# Clk_recovery.net
KiCad netlist of a schematic drawn in Altium Designer
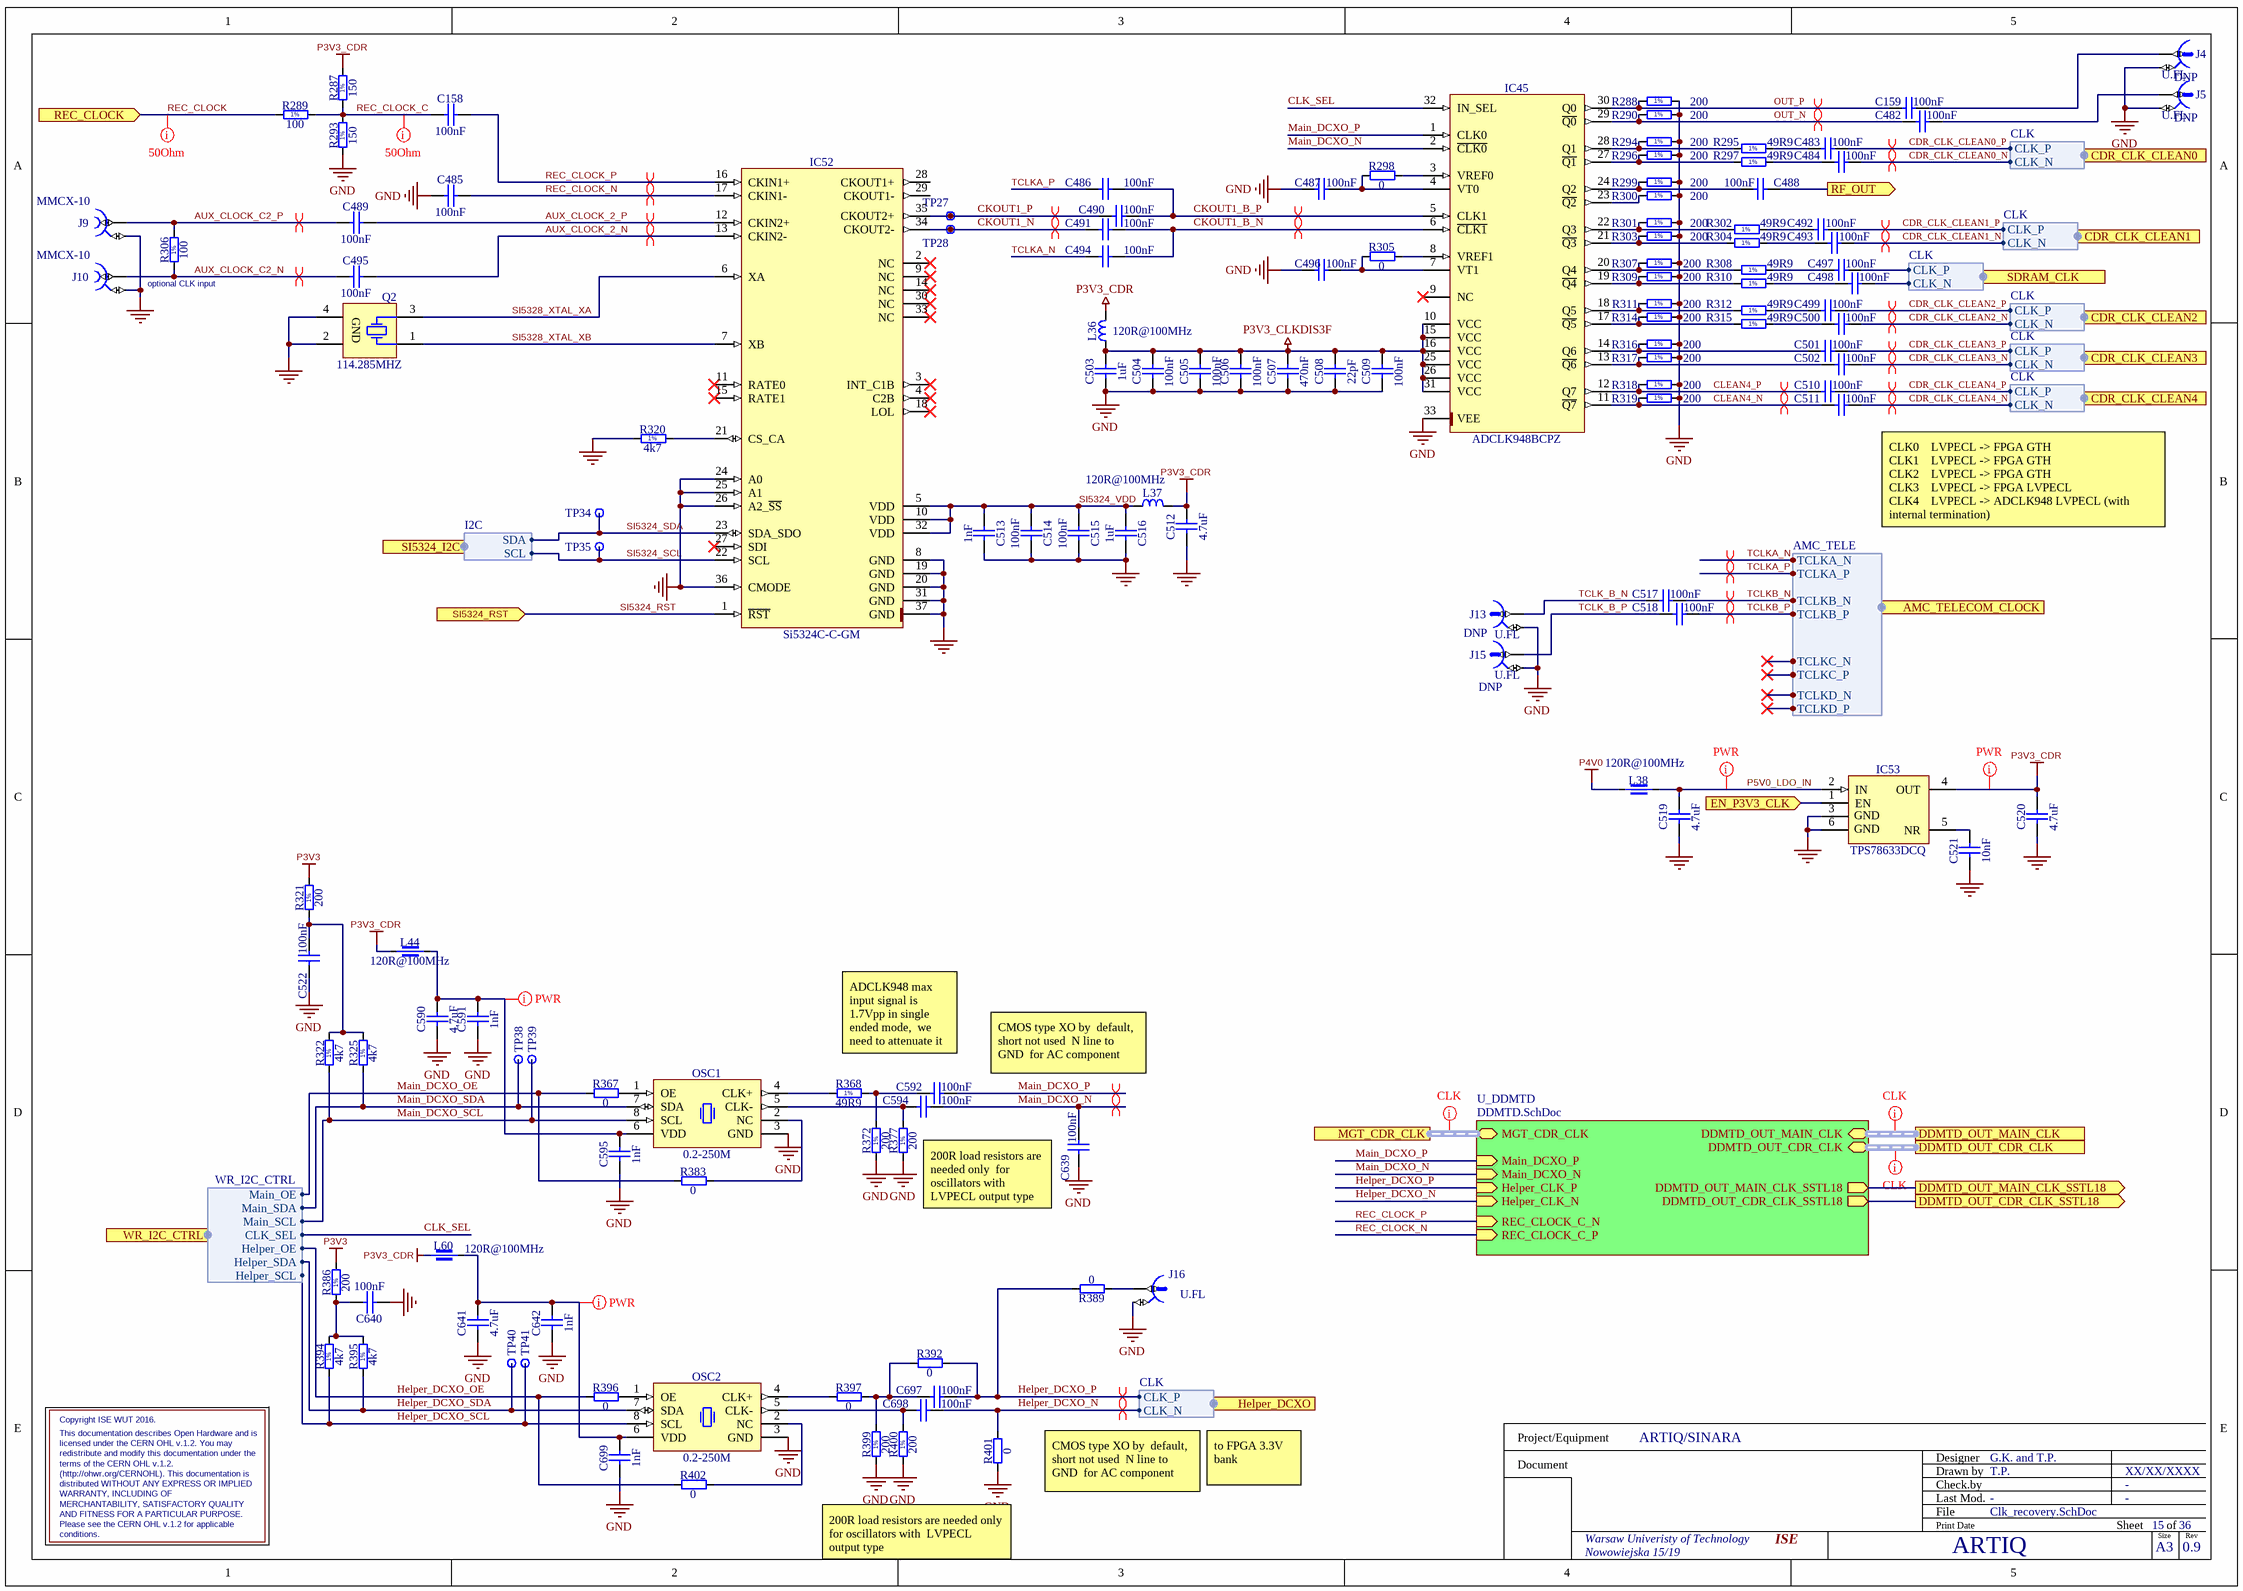
[diagram p0: Clk_recovery.SchDoc]

(export (version "E")
  (design (tool "Eeschema 10.0.6"))
  (components
    (comp (ref "C158")
      (value "100nF")
      (footprint "CAPC0603X33N")
      (description "Non-polarised capacitor")
      (fields
        (field (name "MANUFACTURER PART NUMBER") "CC0201_100NF_6.3V_10%_X5R")
        (field (name "MANUFACTURER") "GENERIC")
        (field (name "AUTHOR") "CERN DEM JLC")
      )
      (libsource (lib "Capacitors") (part "Capacitor - non polarized"))
    )
    (comp (ref "C159")
      (value "100nF")
      (footprint "CAPC0603X33N")
      (description "Non-polarised capacitor")
      (fields
        (field (name "MANUFACTURER PART NUMBER") "CC0201_100NF_6.3V_10%_X5R")
        (field (name "MANUFACTURER") "GENERIC")
        (field (name "AUTHOR") "CERN DEM JLC")
      )
      (libsource (lib "Capacitors") (part "Capacitor - non polarized"))
    )
    (comp (ref "C482")
      (value "100nF")
      (footprint "CAPC0603X33N")
      (description "Non-polarised capacitor")
      (fields
        (field (name "MANUFACTURER PART NUMBER") "CC0201_100NF_6.3V_10%_X5R")
        (field (name "MANUFACTURER") "GENERIC")
        (field (name "AUTHOR") "CERN DEM JLC")
      )
      (libsource (lib "Capacitors") (part "Capacitor - non polarized"))
    )
    (comp (ref "C483")
      (value "100nF")
      (footprint "CAPC0603X33N")
      (description "Non-polarised capacitor")
      (fields
        (field (name "MANUFACTURER PART NUMBER") "CC0201_100NF_6.3V_10%_X5R")
        (field (name "MANUFACTURER") "GENERIC")
        (field (name "AUTHOR") "CERN DEM JLC")
      )
      (libsource (lib "Capacitors") (part "Capacitor - non polarized"))
    )
    (comp (ref "C484")
      (value "100nF")
      (footprint "CAPC0603X33N")
      (description "Non-polarised capacitor")
      (fields
        (field (name "MANUFACTURER PART NUMBER") "CC0201_100NF_6.3V_10%_X5R")
        (field (name "MANUFACTURER") "GENERIC")
        (field (name "AUTHOR") "CERN DEM JLC")
      )
      (libsource (lib "Capacitors") (part "Capacitor - non polarized"))
    )
    (comp (ref "C485")
      (value "100nF")
      (footprint "CAPC0603X33N")
      (description "Non-polarised capacitor")
      (fields
        (field (name "MANUFACTURER PART NUMBER") "CC0201_100NF_6.3V_10%_X5R")
        (field (name "MANUFACTURER") "GENERIC")
        (field (name "AUTHOR") "CERN DEM JLC")
      )
      (libsource (lib "Capacitors") (part "Capacitor - non polarized"))
    )
    (comp (ref "C486")
      (value "100nF")
      (footprint "CAPC0603X33N")
      (description "Non-polarised capacitor")
      (fields
        (field (name "PART NUMBER") "CC0201_100NF_6.3V_10%_X5R")
        (field (name "VOLTAGE") "6.3V")
        (field (name "AUTHOR") "CERN DEM JLC")
      )
      (libsource (lib "Capacitors") (part "Capacitor - non polarized"))
    )
    (comp (ref "C487")
      (value "100nF")
      (footprint "CAPC0603X33N")
      (description "Non-polarised capacitor")
      (fields
        (field (name "PART NUMBER") "CC0201_100NF_6.3V_10%_X5R")
        (field (name "VOLTAGE") "6.3V")
        (field (name "AUTHOR") "CERN DEM JLC")
      )
      (libsource (lib "Capacitors") (part "Capacitor - non polarized"))
    )
    (comp (ref "C488")
      (value "100nF")
      (footprint "CAPC0603X33N")
      (description "Non-polarised capacitor")
      (fields
        (field (name "MANUFACTURER PART NUMBER") "CC0201_100NF_6.3V_10%_X5R")
        (field (name "MANUFACTURER") "GENERIC")
        (field (name "AUTHOR") "CERN DEM JLC")
      )
      (libsource (lib "Capacitors") (part "Capacitor - non polarized"))
    )
    (comp (ref "C489")
      (value "100nF")
      (footprint "CAPC0603X33N")
      (description "Non-polarised capacitor")
      (fields
        (field (name "MANUFACTURER PART NUMBER") "CC0201_100NF_6.3V_10%_X5R")
        (field (name "MANUFACTURER") "GENERIC")
        (field (name "AUTHOR") "CERN DEM JLC")
      )
      (libsource (lib "Capacitors") (part "Capacitor - non polarized"))
    )
    (comp (ref "C490")
      (value "100nF")
      (footprint "CAPC0603X33N")
      (description "Non-polarised capacitor")
      (fields
        (field (name "PART NUMBER") "CC0201_100NF_6.3V_10%_X5R")
        (field (name "VOLTAGE") "6.3V")
        (field (name "AUTHOR") "CERN DEM JLC")
      )
      (libsource (lib "Capacitors") (part "Capacitor - non polarized"))
    )
    (comp (ref "C491")
      (value "100nF")
      (footprint "CAPC0603X33N")
      (description "Non-polarised capacitor")
      (fields
        (field (name "PART NUMBER") "CC0201_100NF_6.3V_10%_X5R")
        (field (name "VOLTAGE") "6.3V")
        (field (name "AUTHOR") "CERN DEM JLC")
      )
      (libsource (lib "Capacitors") (part "Capacitor - non polarized"))
    )
    (comp (ref "C492")
      (value "100nF")
      (footprint "CAPC0603X33N")
      (description "Non-polarised capacitor")
      (fields
        (field (name "MANUFACTURER PART NUMBER") "CC0201_100NF_6.3V_10%_X5R")
        (field (name "MANUFACTURER") "GENERIC")
        (field (name "AUTHOR") "CERN DEM JLC")
      )
      (libsource (lib "Capacitors") (part "Capacitor - non polarized"))
    )
    (comp (ref "C493")
      (value "100nF")
      (footprint "CAPC0603X33N")
      (description "Non-polarised capacitor")
      (fields
        (field (name "MANUFACTURER PART NUMBER") "CC0201_100NF_6.3V_10%_X5R")
        (field (name "MANUFACTURER") "GENERIC")
        (field (name "AUTHOR") "CERN DEM JLC")
      )
      (libsource (lib "Capacitors") (part "Capacitor - non polarized"))
    )
    (comp (ref "C494")
      (value "100nF")
      (footprint "CAPC0603X33N")
      (description "Non-polarised capacitor")
      (fields
        (field (name "PART NUMBER") "CC0201_100NF_6.3V_10%_X5R")
        (field (name "VOLTAGE") "6.3V")
        (field (name "AUTHOR") "CERN DEM JLC")
      )
      (libsource (lib "Capacitors") (part "Capacitor - non polarized"))
    )
    (comp (ref "C495")
      (value "100nF")
      (footprint "CAPC0603X33N")
      (description "Non-polarised capacitor")
      (fields
        (field (name "MANUFACTURER PART NUMBER") "CC0201_100NF_6.3V_10%_X5R")
        (field (name "MANUFACTURER") "GENERIC")
        (field (name "AUTHOR") "CERN DEM JLC")
      )
      (libsource (lib "Capacitors") (part "Capacitor - non polarized"))
    )
    (comp (ref "C496")
      (value "100nF")
      (footprint "CAPC0603X33N")
      (description "Non-polarised capacitor")
      (fields
        (field (name "PART NUMBER") "CC0201_100NF_6.3V_10%_X5R")
        (field (name "VOLTAGE") "6.3V")
        (field (name "AUTHOR") "CERN DEM JLC")
      )
      (libsource (lib "Capacitors") (part "Capacitor - non polarized"))
    )
    (comp (ref "C497")
      (value "100nF")
      (footprint "CAPC0603X33N")
      (description "Non-polarised capacitor")
      (fields
        (field (name "MANUFACTURER PART NUMBER") "CC0201_100NF_6.3V_10%_X5R")
        (field (name "MANUFACTURER") "GENERIC")
        (field (name "AUTHOR") "CERN DEM JLC")
      )
      (libsource (lib "Capacitors") (part "Capacitor - non polarized"))
    )
    (comp (ref "C498")
      (value "100nF")
      (footprint "CAPC0603X33N")
      (description "Non-polarised capacitor")
      (fields
        (field (name "MANUFACTURER PART NUMBER") "CC0201_100NF_6.3V_10%_X5R")
        (field (name "MANUFACTURER") "GENERIC")
        (field (name "AUTHOR") "CERN DEM JLC")
      )
      (libsource (lib "Capacitors") (part "Capacitor - non polarized"))
    )
    (comp (ref "C499")
      (value "100nF")
      (footprint "CAPC0603X33N")
      (description "Non-polarised capacitor")
      (fields
        (field (name "MANUFACTURER PART NUMBER") "CC0201_100NF_6.3V_10%_X5R")
        (field (name "MANUFACTURER") "GENERIC")
        (field (name "AUTHOR") "CERN DEM JLC")
      )
      (libsource (lib "Capacitors") (part "Capacitor - non polarized"))
    )
    (comp (ref "C500")
      (value "100nF")
      (footprint "CAPC0603X33N")
      (description "Non-polarised capacitor")
      (fields
        (field (name "MANUFACTURER PART NUMBER") "CC0201_100NF_6.3V_10%_X5R")
        (field (name "MANUFACTURER") "GENERIC")
        (field (name "AUTHOR") "CERN DEM JLC")
      )
      (libsource (lib "Capacitors") (part "Capacitor - non polarized"))
    )
    (comp (ref "C501")
      (value "100nF")
      (footprint "CAPC0603X33N")
      (description "Non-polarised capacitor")
      (fields
        (field (name "MANUFACTURER PART NUMBER") "CC0201_100NF_6.3V_10%_X5R")
        (field (name "MANUFACTURER") "GENERIC")
        (field (name "AUTHOR") "CERN DEM JLC")
      )
      (libsource (lib "Capacitors") (part "Capacitor - non polarized"))
    )
    (comp (ref "C502")
      (value "100nF")
      (footprint "CAPC0603X33N")
      (description "Non-polarised capacitor")
      (fields
        (field (name "MANUFACTURER PART NUMBER") "CC0201_100NF_6.3V_10%_X5R")
        (field (name "MANUFACTURER") "GENERIC")
        (field (name "AUTHOR") "CERN DEM JLC")
      )
      (libsource (lib "Capacitors") (part "Capacitor - non polarized"))
    )
    (comp (ref "C503")
      (value "1uF")
      (footprint "CAPC1005X55N")
      (description "Non-polarised capacitor")
      (fields
        (field (name "PART NUMBER") "CC0402_1UF_16V_10%_X5R")
        (field (name "VOLTAGE") "16V")
        (field (name "AUTHOR") "CERN DEM JLC")
      )
      (libsource (lib "Capacitors") (part "Capacitor - non polarized"))
    )
    (comp (ref "C504")
      (value "100nF")
      (footprint "CAPC0603X33N")
      (description "Non-polarised capacitor")
      (fields
        (field (name "PART NUMBER") "CC0201_100NF_6.3V_10%_X5R")
        (field (name "VOLTAGE") "6.3V")
        (field (name "AUTHOR") "CERN DEM JLC")
      )
      (libsource (lib "Capacitors") (part "Capacitor - non polarized"))
    )
    (comp (ref "C505")
      (value "100nF")
      (footprint "CAPC0603X33N")
      (description "Non-polarised capacitor")
      (fields
        (field (name "PART NUMBER") "CC0201_100NF_6.3V_10%_X5R")
        (field (name "VOLTAGE") "6.3V")
        (field (name "AUTHOR") "CERN DEM JLC")
      )
      (libsource (lib "Capacitors") (part "Capacitor - non polarized"))
    )
    (comp (ref "C506")
      (value "100nF")
      (footprint "CAPC0603X33N")
      (description "Non-polarised capacitor")
      (fields
        (field (name "PART NUMBER") "CC0201_100NF_6.3V_10%_X5R")
        (field (name "VOLTAGE") "6.3V")
        (field (name "AUTHOR") "CERN DEM JLC")
      )
      (libsource (lib "Capacitors") (part "Capacitor - non polarized"))
    )
    (comp (ref "C507")
      (value "470nF")
      (footprint "CAPC1005X55N")
      (description "Non-polarised capacitor")
      (fields
        (field (name "PART NUMBER") "CC0402_470NF_16V_10%_X5R")
        (field (name "VOLTAGE") "16V")
        (field (name "AUTHOR") "CERN DEM JLC")
      )
      (libsource (lib "Capacitors") (part "Capacitor - non polarized"))
    )
    (comp (ref "C508")
      (value "22pF")
      (footprint "CAPC1005X55N")
      (description "Non-polarised capacitor")
      (fields
        (field (name "PART NUMBER") "CC0402_22PF_50V_5%_C0G")
        (field (name "VOLTAGE") "50V")
        (field (name "AUTHOR") "CERN DEM JLC")
      )
      (libsource (lib "Capacitors") (part "Capacitor - non polarized"))
    )
    (comp (ref "C509")
      (value "100nF")
      (footprint "CAPC0603X33N")
      (description "Non-polarised capacitor")
      (fields
        (field (name "PART NUMBER") "CC0201_100NF_6.3V_10%_X5R")
        (field (name "VOLTAGE") "6.3V")
        (field (name "AUTHOR") "CERN DEM JLC")
      )
      (libsource (lib "Capacitors") (part "Capacitor - non polarized"))
    )
    (comp (ref "C510")
      (value "100nF")
      (footprint "CAPC0603X33N")
      (description "Non-polarised capacitor")
      (fields
        (field (name "MANUFACTURER PART NUMBER") "CC0201_100NF_6.3V_10%_X5R")
        (field (name "MANUFACTURER") "GENERIC")
        (field (name "AUTHOR") "CERN DEM JLC")
      )
      (libsource (lib "Capacitors") (part "Capacitor - non polarized"))
    )
    (comp (ref "C511")
      (value "100nF")
      (footprint "CAPC0603X33N")
      (description "Non-polarised capacitor")
      (fields
        (field (name "MANUFACTURER PART NUMBER") "CC0201_100NF_6.3V_10%_X5R")
        (field (name "MANUFACTURER") "GENERIC")
        (field (name "AUTHOR") "CERN DEM JLC")
      )
      (libsource (lib "Capacitors") (part "Capacitor - non polarized"))
    )
    (comp (ref "C512")
      (value "4.7uF")
      (footprint "CAPC1608X90N")
      (description "Non-polarised capacitor")
      (fields
        (field (name "MANUFACTURER PART NUMBER") "CC0603_4.7UF_25V_10%_X5R")
        (field (name "MANUFACTURER") "GENERIC")
        (field (name "AUTHOR") "CERN DEM JLC")
      )
      (libsource (lib "Capacitors") (part "Capacitor - non polarized"))
    )
    (comp (ref "C513")
      (value "1nF")
      (footprint "CAPC0603X33N")
      (description "Non-polarised capacitor")
      (fields
        (field (name "MANUFACTURER PART NUMBER") "CC0201_1NF_16V_10%_X5R")
        (field (name "MANUFACTURER") "GENERIC")
        (field (name "AUTHOR") "CERN DEM JLC")
      )
      (libsource (lib "Capacitors") (part "Capacitor - non polarized"))
    )
    (comp (ref "C514")
      (value "100nF")
      (footprint "CAPC0603X33N")
      (description "Non-polarised capacitor")
      (fields
        (field (name "MANUFACTURER PART NUMBER") "CC0201_100NF_6.3V_10%_X5R")
        (field (name "MANUFACTURER") "GENERIC")
        (field (name "AUTHOR") "CERN DEM JLC")
      )
      (libsource (lib "Capacitors") (part "Capacitor - non polarized"))
    )
    (comp (ref "C515")
      (value "100nF")
      (footprint "CAPC0603X33N")
      (description "Non-polarised capacitor")
      (fields
        (field (name "MANUFACTURER PART NUMBER") "CC0201_100NF_6.3V_10%_X5R")
        (field (name "MANUFACTURER") "GENERIC")
        (field (name "AUTHOR") "CERN DEM JLC")
      )
      (libsource (lib "Capacitors") (part "Capacitor - non polarized"))
    )
    (comp (ref "C516")
      (value "1uF")
      (footprint "CAPC1005X55N")
      (description "Non-polarised capacitor")
      (fields
        (field (name "MANUFACTURER PART NUMBER") "CC0402_1UF_16V_10%_X5R")
        (field (name "MANUFACTURER") "GENERIC")
        (field (name "AUTHOR") "CERN DEM JLC")
      )
      (libsource (lib "Capacitors") (part "Capacitor - non polarized"))
    )
    (comp (ref "C517")
      (value "100nF")
      (footprint "CAPC0603X33N")
      (description "Non-polarised capacitor")
      (fields
        (field (name "MANUFACTURER PART NUMBER") "CC0201_100NF_6.3V_10%_X5R")
        (field (name "MANUFACTURER") "GENERIC")
        (field (name "AUTHOR") "CERN DEM JLC")
      )
      (libsource (lib "Capacitors") (part "Capacitor - non polarized"))
    )
    (comp (ref "C518")
      (value "100nF")
      (footprint "CAPC0603X33N")
      (description "Non-polarised capacitor")
      (fields
        (field (name "MANUFACTURER PART NUMBER") "CC0201_100NF_6.3V_10%_X5R")
        (field (name "MANUFACTURER") "GENERIC")
        (field (name "AUTHOR") "CERN DEM JLC")
      )
      (libsource (lib "Capacitors") (part "Capacitor - non polarized"))
    )
    (comp (ref "C519")
      (value "4.7uF")
      (footprint "CAPC1608X90N")
      (description "Non-polarised capacitor")
      (fields
        (field (name "MANUFACTURER PART NUMBER") "CC0603_4.7UF_25V_10%_X5R")
        (field (name "MANUFACTURER") "GENERIC")
        (field (name "AUTHOR") "CERN DEM JLC")
      )
      (libsource (lib "Capacitors") (part "Capacitor - non polarized"))
    )
    (comp (ref "C520")
      (value "4.7uF")
      (footprint "CAPC1608X90N")
      (description "Non-polarised capacitor")
      (fields
        (field (name "MANUFACTURER PART NUMBER") "CC0603_4.7UF_25V_10%_X5R")
        (field (name "MANUFACTURER") "GENERIC")
        (field (name "AUTHOR") "CERN DEM JLC")
      )
      (libsource (lib "Capacitors") (part "Capacitor - non polarized"))
    )
    (comp (ref "C521")
      (value "10nF")
      (footprint "CAPC1608X87N")
      (description "Non-polarised capacitor")
      (fields
        (field (name "PART NUMBER") "CC0603_10NF_50V_5%_C0G")
        (field (name "VOLTAGE") "50V")
        (field (name "AUTHOR") "CERN DEM JLC")
      )
      (libsource (lib "Capacitors") (part "Capacitor - non polarized"))
    )
    (comp (ref "C522")
      (value "100nF")
      (footprint "CAPC0603X33N")
      (description "Non-polarised capacitor")
      (fields
        (field (name "PART NUMBER") "CC0201_100NF_6.3V_10%_X5R")
        (field (name "VOLTAGE") "6.3V")
        (field (name "AUTHOR") "CERN DEM JLC")
      )
      (libsource (lib "Capacitors") (part "Capacitor - non polarized"))
    )
    (comp (ref "C590")
      (value "4.7uF")
      (footprint "CAPC1608X90N")
      (description "Non-polarised capacitor")
      (fields
        (field (name "PART NUMBER") "CC0603_4.7UF_25V_10%_X5R")
        (field (name "VOLTAGE") "25V")
        (field (name "AUTHOR") "CERN DEM JLC")
      )
      (libsource (lib "Capacitors") (part "Capacitor - non polarized"))
    )
    (comp (ref "C591")
      (value "1nF")
      (footprint "CAPC0603X33N")
      (description "Non-polarised capacitor")
      (fields
        (field (name "PART NUMBER") "CC0201_1NF_16V_10%_X5R")
        (field (name "VOLTAGE") "16V")
        (field (name "AUTHOR") "CERN DEM JLC")
      )
      (libsource (lib "Capacitors") (part "Capacitor - non polarized"))
    )
    (comp (ref "C592")
      (value "100nF")
      (footprint "CAPC0603X33N")
      (description "Non-polarised capacitor")
      (fields
        (field (name "PART NUMBER") "CC0201_100NF_6.3V_10%_X5R")
        (field (name "VOLTAGE") "6.3V")
        (field (name "AUTHOR") "CERN DEM JLC")
      )
      (libsource (lib "Capacitors") (part "Capacitor - non polarized"))
    )
    (comp (ref "C594")
      (value "100nF")
      (footprint "CAPC0603X33N")
      (description "Non-polarised capacitor")
      (fields
        (field (name "PART NUMBER") "CC0201_100NF_6.3V_10%_X5R")
        (field (name "VOLTAGE") "6.3V")
        (field (name "AUTHOR") "CERN DEM JLC")
      )
      (libsource (lib "Capacitors") (part "Capacitor - non polarized"))
    )
    (comp (ref "C595")
      (value "1nF")
      (footprint "CAPC0603X33N")
      (description "Non-polarised capacitor")
      (fields
        (field (name "PART NUMBER") "CC0201_1NF_16V_10%_X5R")
        (field (name "VOLTAGE") "16V")
        (field (name "AUTHOR") "CERN DEM JLC")
      )
      (libsource (lib "Capacitors") (part "Capacitor - non polarized"))
    )
    (comp (ref "C639")
      (value "100nF")
      (footprint "CAPC0603X33N")
      (description "Non-polarised capacitor")
      (fields
        (field (name "PART NUMBER") "CC0201_100NF_6.3V_10%_X5R")
        (field (name "VOLTAGE") "6.3V")
        (field (name "AUTHOR") "CERN DEM JLC")
      )
      (libsource (lib "Capacitors") (part "Capacitor - non polarized"))
    )
    (comp (ref "C640")
      (value "100nF")
      (footprint "CAPC0603X33N")
      (description "Non-polarised capacitor")
      (fields
        (field (name "MANUFACTURER PART NUMBER") "CC0201_100NF_6.3V_10%_X5R")
        (field (name "MANUFACTURER") "GENERIC")
        (field (name "AUTHOR") "CERN DEM JLC")
      )
      (libsource (lib "Capacitors") (part "Capacitor - non polarized"))
    )
    (comp (ref "C641")
      (value "4.7uF")
      (footprint "CAPC1608X90N")
      (description "Non-polarised capacitor")
      (fields
        (field (name "PART NUMBER") "CC0603_4.7UF_25V_10%_X5R")
        (field (name "VOLTAGE") "25V")
        (field (name "AUTHOR") "CERN DEM JLC")
      )
      (libsource (lib "Capacitors") (part "Capacitor - non polarized"))
    )
    (comp (ref "C642")
      (value "1nF")
      (footprint "CAPC0603X33N")
      (description "Non-polarised capacitor")
      (fields
        (field (name "PART NUMBER") "CC0201_1NF_16V_10%_X5R")
        (field (name "VOLTAGE") "16V")
        (field (name "AUTHOR") "CERN DEM JLC")
      )
      (libsource (lib "Capacitors") (part "Capacitor - non polarized"))
    )
    (comp (ref "C697")
      (value "100nF")
      (footprint "CAPC0603X33N")
      (description "Non-polarised capacitor")
      (fields
        (field (name "PART NUMBER") "CC0201_100NF_6.3V_10%_X5R")
        (field (name "VOLTAGE") "6.3V")
        (field (name "AUTHOR") "CERN DEM JLC")
      )
      (libsource (lib "Capacitors") (part "Capacitor - non polarized"))
    )
    (comp (ref "C698")
      (value "100nF")
      (footprint "CAPC0603X33N")
      (description "Non-polarised capacitor")
      (fields
        (field (name "PART NUMBER") "CC0201_100NF_6.3V_10%_X5R")
        (field (name "VOLTAGE") "6.3V")
        (field (name "AUTHOR") "CERN DEM JLC")
      )
      (libsource (lib "Capacitors") (part "Capacitor - non polarized"))
    )
    (comp (ref "C699")
      (value "1nF")
      (footprint "CAPC0603X33N")
      (description "Non-polarised capacitor")
      (fields
        (field (name "PART NUMBER") "CC0201_1NF_16V_10%_X5R")
        (field (name "VOLTAGE") "16V")
        (field (name "AUTHOR") "CERN DEM JLC")
      )
      (libsource (lib "Capacitors") (part "Capacitor - non polarized"))
    )
    (comp (ref "IC45")
      (value "ADCLK948BCPZ")
      (footprint "QFN50P500X500X80-33N-S285")
      (description "Two Selectable Inputs, 8 LVPECL Outputs, SiGe Clock Fanout Buffer")
      (fields (field (name "MANUFACTURER") "ANALOG DEVICES") (field (name "AUTHOR") "CERN DEM MR"))
      (libsource (lib "ICs And Semiconductors") (part "ADCLK948"))
    )
    (comp (ref "IC52")
      (value "Si5324C-C-GM")
      (footprint "QFN50P600X600X90-37N-S425")
      (description "Any Frequency Precision Clock Multiplier/Jitter Attenuator")
      (fields (field (name "MANUFACTURER") "SILICON LABS") (field (name "AUTHOR") "CERN DEM JLC"))
      (libsource (lib "ICs And Semiconductors") (part "Si5324"))
    )
    (comp (ref "IC53")
      (value "TPS78633DCQ")
      (footprint "SOT127P700X180-6N")
      (description "Ultralow-Noise, High-PSRR, Fast, RF, 1.5A Low-Dropout Linear Regulator")
      (fields (field (name "MANUFACTURER") "TEXAS INSTRUMENTS") (field (name "AUTHOR") "CERN DEM JMW"))
      (libsource (lib "ICs And Semiconductors") (part "TPS786xxDCQ"))
    )
    (comp (ref "J4")
      (value "U.FL")
      (footprint "HIROSE_U.FL-R-SMT-1(10)")
      (fields
        (field (name "PART NUMBER") "HIROSE_U.FL-R-SMT-1(10)")
        (field (name "MANUFACTURER") "HIROSE (HRS)")
        (field (name "MANUFACTURER PART NUMBER") "U.FL-R-SMT-1(10)")
        (field (name "ALTIUM_VALUE") "DNP")
        (field (name "AUTHOR") "CERN DEM JLC")
      )
      (libsource (lib "") (part "Coax_1Male_1Shield_1"))
    )
    (comp (ref "J5")
      (value "U.FL")
      (footprint "HIROSE_U.FL-R-SMT-1(10)")
      (fields
        (field (name "PART NUMBER") "HIROSE_U.FL-R-SMT-1(10)")
        (field (name "MANUFACTURER") "HIROSE (HRS)")
        (field (name "MANUFACTURER PART NUMBER") "U.FL-R-SMT-1(10)")
        (field (name "ALTIUM_VALUE") "DNP")
        (field (name "AUTHOR") "CERN DEM JLC")
      )
      (libsource (lib "") (part "Coax_1Male_1Shield_1"))
    )
    (comp (ref "J9")
      (value "Coax_1Female_1Shield")
      (footprint "NINIGI_MMCX-10")
      (fields
        (field (name "PART NUMBER") "MMCX-10")
        (field (name "MANUFACTURER") "NINIGI")
        (field (name "MANUFACTURER PART NUMBER") "NINIGI MMCX-10")
        (field (name "AUTHOR") "GK")
      )
      (libsource (lib "LIBRARY_SCH") (part "CON_RF_MMCX"))
    )
    (comp (ref "J10")
      (value "Coax_1Female_1Shield")
      (footprint "NINIGI_MMCX-10")
      (fields
        (field (name "PART NUMBER") "MMCX-10")
        (field (name "MANUFACTURER") "NINIGI")
        (field (name "MANUFACTURER PART NUMBER") "NINIGI MMCX-10")
        (field (name "AUTHOR") "GK")
      )
      (libsource (lib "LIBRARY_SCH") (part "CON_RF_MMCX"))
    )
    (comp (ref "J13")
      (value "U.FL")
      (footprint "HIROSE_U.FL-R-SMT-1(10)")
      (fields
        (field (name "PART NUMBER") "HIROSE_U.FL-R-SMT-1(10)")
        (field (name "MANUFACTURER") "HIROSE (HRS)")
        (field (name "MANUFACTURER PART NUMBER") "U.FL-R-SMT-1(10)")
        (field (name "ALTIUM_VALUE") "DNP")
        (field (name "AUTHOR") "CERN DEM JLC")
      )
      (libsource (lib "Connectors") (part "Coax_1Male_1Shield"))
    )
    (comp (ref "J15")
      (value "U.FL")
      (footprint "HIROSE_U.FL-R-SMT-1(10)")
      (fields
        (field (name "PART NUMBER") "HIROSE_U.FL-R-SMT-1(10)")
        (field (name "MANUFACTURER") "HIROSE (HRS)")
        (field (name "MANUFACTURER PART NUMBER") "U.FL-R-SMT-1(10)")
        (field (name "ALTIUM_VALUE") "DNP")
        (field (name "AUTHOR") "CERN DEM JLC")
      )
      (libsource (lib "Connectors") (part "Coax_1Male_1Shield"))
    )
    (comp (ref "J16")
      (value "U.FL")
      (footprint "HIROSE_U.FL-R-SMT-1(10)")
      (fields
        (field (name "MANUFACTURER PART NUMBER") "U.FL-R-SMT-1(10)")
        (field (name "MANUFACTURER") "HIROSE (HRS)")
        (field (name "PART NUMBER") "HIROSE_U.FL-R-SMT-1(10)")
        (field (name "AUTHOR") "CERN DEM JLC")
      )
      (libsource (lib "") (part "Coax_1Male_1Shield_1"))
    )
    (comp (ref "L36")
      (value "120R@100MHz")
      (footprint "INDC1608X95N")
      (description "Inductor")
      (fields
        (field (name "PART NUMBER") "IND0603_MURATA_BLM18PG121SN1D")
        (field (name "POWER") "2A")
        (field (name "AUTHOR") "CERN DEM BC")
      )
      (libsource (lib "") (part "Inductor_1"))
    )
    (comp (ref "L37")
      (value "120R@100MHz")
      (footprint "INDC1608X95N")
      (description "Inductor")
      (fields
        (field (name "MANUFACTURER PART NUMBER") "BLM18PG121SN1D")
        (field (name "MANUFACTURER") "MURATA")
        (field (name "AUTHOR") "CERN DEM BC")
      )
      (libsource (lib "Inductors & Transformers") (part "Inductor"))
    )
    (comp (ref "L38")
      (value "120R@100MHz")
      (footprint "INDC1608X95N")
      (fields
        (field (name "MANUFACTURER PART NUMBER") "BLM18PG121SN1D")
        (field (name "MANUFACTURER") "MURATA")
        (field (name "PART NUMBER") "IND0603_MURATA_BLM18PG121SN1D")
        (field (name "AUTHOR") "CERN DEM BC")
      )
      (libsource (lib "Inductors & Transformers") (part "Ferrite Bead"))
    )
    (comp (ref "L44")
      (value "120R@100MHz")
      (footprint "INDC1608X95N")
      (fields
        (field (name "PART NUMBER") "IND0603_MURATA_BLM18PG121SN1D")
        (field (name "POWER") "2A")
        (field (name "MANUFACTURER") "MURATA")
        (field (name "AUTHOR") "CERN DEM BC")
      )
      (libsource (lib "Inductors & Transformers") (part "Ferrite Bead"))
    )
    (comp (ref "L60")
      (value "120R@100MHz")
      (footprint "INDC1608X95N")
      (fields
        (field (name "PART NUMBER") "IND0603_MURATA_BLM18PG121SN1D")
        (field (name "POWER") "2A")
        (field (name "MANUFACTURER") "MURATA")
        (field (name "AUTHOR") "CERN DEM BC")
      )
      (libsource (lib "Inductors & Transformers") (part "Ferrite Bead"))
    )
    (comp (ref "OSC1")
      (value "0.2-250M")
      (footprint "OSC_SILICON-LAB_SI570")
      (description "Ultra Low Jitter I2C Programmable XO (95 fs), 0.2 to 250MHz")
      (fields
        (field (name "MANUFACTURER") "Silabs")
        (field (name "MANUFACTURER PART NUMBER") "549CBAC000112ABG")
      )
      (libsource (lib "TP_LIB") (part "549CBAC000112ABG"))
    )
    (comp (ref "OSC2")
      (value "0.2-250M")
      (footprint "OSC_SILICON-LAB_SI570")
      (description "Ultra Low Jitter I2C Programmable XO (95 fs), 0.2 to 250MHz")
      (fields
        (field (name "MANUFACTURER") "Silabs")
        (field (name "MANUFACTURER PART NUMBER") "549CBAC000112ABG")
      )
      (libsource (lib "TP_LIB") (part "549CBAC000112ABG"))
    )
    (comp (ref "Q2")
      (value "114.285MHZ")
      (footprint "XTAL_CONNOR_CS")
      (description "Crystal 4 pins 1=XTAL Control 2=GND3=XTAL 4=GND")
      (fields
        (field (name "MANUFACTURER PART NUMBER") "CS-023-114.285M")
        (field (name "MANUFACTURER") "CONNOR-WINFIELD")
        (field (name "AUTHOR") "CERN DEM JLC")
      )
      (libsource (lib "ICs And Semiconductors") (part "Quartz Crystal 1X 2GND 3X 4GND"))
    )
    (comp (ref "R287")
      (value "150")
      (footprint "RESC1005X40N")
      (description "Resistor - 1%")
      (fields
        (field (name "PART NUMBER") "R0402_150R_1%_0.0625W_100PPM")
        (field (name "POWER") "0.0625W")
        (field (name "AUTHOR") "CERN DEM JLC")
      )
      (libsource (lib "Resistors") (part "Resistor - 1%"))
    )
    (comp (ref "R288")
      (value "200")
      (footprint "RESC1005X40N")
      (description "Resistor - 1%")
      (fields
        (field (name "MANUFACTURER PART NUMBER") "R0402_200R_1%_0.0625W_100PPM")
        (field (name "MANUFACTURER") "GENERIC")
        (field (name "AUTHOR") "CERN DEM JLC")
      )
      (libsource (lib "Resistors") (part "Resistor - 1%"))
    )
    (comp (ref "R289")
      (value "100")
      (footprint "RESC1005X40N")
      (description "Resistor - 1%")
      (fields
        (field (name "MANUFACTURER PART NUMBER") "R0402_100R_1%_0.0625W_100PPM")
        (field (name "MANUFACTURER") "GENERIC")
        (field (name "AUTHOR") "CERN DEM JLC")
      )
      (libsource (lib "Resistors") (part "Resistor - 1%"))
    )
    (comp (ref "R290")
      (value "200")
      (footprint "RESC1005X40N")
      (description "Resistor - 1%")
      (fields
        (field (name "MANUFACTURER PART NUMBER") "R0402_200R_1%_0.0625W_100PPM")
        (field (name "MANUFACTURER") "GENERIC")
        (field (name "AUTHOR") "CERN DEM JLC")
      )
      (libsource (lib "Resistors") (part "Resistor - 1%"))
    )
    (comp (ref "R293")
      (value "150")
      (footprint "RESC1005X40N")
      (description "Resistor - 1%")
      (fields
        (field (name "PART NUMBER") "R0402_150R_1%_0.0625W_100PPM")
        (field (name "POWER") "0.0625W")
        (field (name "AUTHOR") "CERN DEM JLC")
      )
      (libsource (lib "Resistors") (part "Resistor - 1%"))
    )
    (comp (ref "R294")
      (value "200")
      (footprint "RESC1005X40N")
      (description "Resistor - 1%")
      (fields
        (field (name "MANUFACTURER PART NUMBER") "R0402_200R_1%_0.0625W_100PPM")
        (field (name "MANUFACTURER") "GENERIC")
        (field (name "AUTHOR") "CERN DEM JLC")
      )
      (libsource (lib "Resistors") (part "Resistor - 1%"))
    )
    (comp (ref "R295")
      (value "49R9")
      (footprint "RESC1005X40N")
      (description "Resistor - 1%")
      (fields
        (field (name "MANUFACTURER PART NUMBER") "R0402_49R9_1%_0.0625W_100PPM")
        (field (name "MANUFACTURER") "GENERIC")
        (field (name "AUTHOR") "CERN DEM JLC")
      )
      (libsource (lib "Resistors") (part "Resistor - 1%"))
    )
    (comp (ref "R296")
      (value "200")
      (footprint "RESC1005X40N")
      (description "Resistor - 1%")
      (fields
        (field (name "MANUFACTURER PART NUMBER") "R0402_200R_1%_0.0625W_100PPM")
        (field (name "MANUFACTURER") "GENERIC")
        (field (name "AUTHOR") "CERN DEM JLC")
      )
      (libsource (lib "Resistors") (part "Resistor - 1%"))
    )
    (comp (ref "R297")
      (value "49R9")
      (footprint "RESC1005X40N")
      (description "Resistor - 1%")
      (fields
        (field (name "MANUFACTURER PART NUMBER") "R0402_49R9_1%_0.0625W_100PPM")
        (field (name "MANUFACTURER") "GENERIC")
        (field (name "AUTHOR") "CERN DEM JLC")
      )
      (libsource (lib "Resistors") (part "Resistor - 1%"))
    )
    (comp (ref "R298")
      (value "0")
      (footprint "RESC1005X40N")
      (description "Resistor")
      (fields
        (field (name "PART NUMBER") "R0402_0R_JUMPER")
        (field (name "MANUFACTURER") "GENERIC")
        (field (name "AUTHOR") "CERN DEM JLC")
      )
      (libsource (lib "Resistors") (part "Resistor"))
    )
    (comp (ref "R299")
      (value "200")
      (footprint "RESC1005X40N")
      (description "Resistor - 1%")
      (fields
        (field (name "MANUFACTURER PART NUMBER") "R0402_200R_1%_0.0625W_100PPM")
        (field (name "MANUFACTURER") "GENERIC")
        (field (name "AUTHOR") "CERN DEM JLC")
      )
      (libsource (lib "Resistors") (part "Resistor - 1%"))
    )
    (comp (ref "R300")
      (value "200")
      (footprint "RESC1005X40N")
      (description "Resistor - 1%")
      (fields
        (field (name "MANUFACTURER PART NUMBER") "R0402_200R_1%_0.0625W_100PPM")
        (field (name "MANUFACTURER") "GENERIC")
        (field (name "AUTHOR") "CERN DEM JLC")
      )
      (libsource (lib "Resistors") (part "Resistor - 1%"))
    )
    (comp (ref "R301")
      (value "200")
      (footprint "RESC1005X40N")
      (description "Resistor - 1%")
      (fields
        (field (name "MANUFACTURER PART NUMBER") "R0402_200R_1%_0.0625W_100PPM")
        (field (name "MANUFACTURER") "GENERIC")
        (field (name "AUTHOR") "CERN DEM JLC")
      )
      (libsource (lib "Resistors") (part "Resistor - 1%"))
    )
    (comp (ref "R302")
      (value "49R9")
      (footprint "RESC1005X40N")
      (description "Resistor - 1%")
      (fields
        (field (name "MANUFACTURER PART NUMBER") "R0402_49R9_1%_0.0625W_100PPM")
        (field (name "MANUFACTURER") "GENERIC")
        (field (name "AUTHOR") "CERN DEM JLC")
      )
      (libsource (lib "Resistors") (part "Resistor - 1%"))
    )
    (comp (ref "R303")
      (value "200")
      (footprint "RESC1005X40N")
      (description "Resistor - 1%")
      (fields
        (field (name "MANUFACTURER PART NUMBER") "R0402_200R_1%_0.0625W_100PPM")
        (field (name "MANUFACTURER") "GENERIC")
        (field (name "AUTHOR") "CERN DEM JLC")
      )
      (libsource (lib "Resistors") (part "Resistor - 1%"))
    )
    (comp (ref "R304")
      (value "49R9")
      (footprint "RESC1005X40N")
      (description "Resistor - 1%")
      (fields
        (field (name "MANUFACTURER PART NUMBER") "R0402_49R9_1%_0.0625W_100PPM")
        (field (name "MANUFACTURER") "GENERIC")
        (field (name "AUTHOR") "CERN DEM JLC")
      )
      (libsource (lib "Resistors") (part "Resistor - 1%"))
    )
    (comp (ref "R305")
      (value "0")
      (footprint "RESC1005X40N")
      (description "Resistor")
      (fields
        (field (name "PART NUMBER") "R0402_0R_JUMPER")
        (field (name "MANUFACTURER") "GENERIC")
        (field (name "AUTHOR") "CERN DEM JLC")
      )
      (libsource (lib "Resistors") (part "Resistor"))
    )
    (comp (ref "R306")
      (value "100")
      (footprint "RESC1005X40N")
      (description "Resistor - 1%")
      (fields
        (field (name "MANUFACTURER PART NUMBER") "R0402_100R_1%_0.0625W_100PPM")
        (field (name "MANUFACTURER") "GENERIC")
        (field (name "AUTHOR") "CERN DEM JLC")
      )
      (libsource (lib "Resistors") (part "Resistor - 1%"))
    )
    (comp (ref "R307")
      (value "200")
      (footprint "RESC1005X40N")
      (description "Resistor - 1%")
      (fields
        (field (name "MANUFACTURER PART NUMBER") "R0402_200R_1%_0.0625W_100PPM")
        (field (name "MANUFACTURER") "GENERIC")
        (field (name "AUTHOR") "CERN DEM JLC")
      )
      (libsource (lib "Resistors") (part "Resistor - 1%"))
    )
    (comp (ref "R308")
      (value "49R9")
      (footprint "RESC1005X40N")
      (description "Resistor - 1%")
      (fields
        (field (name "MANUFACTURER PART NUMBER") "R0402_49R9_1%_0.0625W_100PPM")
        (field (name "MANUFACTURER") "GENERIC")
        (field (name "AUTHOR") "CERN DEM JLC")
      )
      (libsource (lib "Resistors") (part "Resistor - 1%"))
    )
    (comp (ref "R309")
      (value "200")
      (footprint "RESC1005X40N")
      (description "Resistor - 1%")
      (fields
        (field (name "MANUFACTURER PART NUMBER") "R0402_200R_1%_0.0625W_100PPM")
        (field (name "MANUFACTURER") "GENERIC")
        (field (name "AUTHOR") "CERN DEM JLC")
      )
      (libsource (lib "Resistors") (part "Resistor - 1%"))
    )
    (comp (ref "R310")
      (value "49R9")
      (footprint "RESC1005X40N")
      (description "Resistor - 1%")
      (fields
        (field (name "MANUFACTURER PART NUMBER") "R0402_49R9_1%_0.0625W_100PPM")
        (field (name "MANUFACTURER") "GENERIC")
        (field (name "AUTHOR") "CERN DEM JLC")
      )
      (libsource (lib "Resistors") (part "Resistor - 1%"))
    )
    (comp (ref "R311")
      (value "200")
      (footprint "RESC1005X40N")
      (description "Resistor - 1%")
      (fields
        (field (name "MANUFACTURER PART NUMBER") "R0402_200R_1%_0.0625W_100PPM")
        (field (name "MANUFACTURER") "GENERIC")
        (field (name "AUTHOR") "CERN DEM JLC")
      )
      (libsource (lib "Resistors") (part "Resistor - 1%"))
    )
    (comp (ref "R312")
      (value "49R9")
      (footprint "RESC1005X40N")
      (description "Resistor - 1%")
      (fields
        (field (name "MANUFACTURER PART NUMBER") "R0402_49R9_1%_0.0625W_100PPM")
        (field (name "MANUFACTURER") "GENERIC")
        (field (name "AUTHOR") "CERN DEM JLC")
      )
      (libsource (lib "Resistors") (part "Resistor - 1%"))
    )
    (comp (ref "R314")
      (value "200")
      (footprint "RESC1005X40N")
      (description "Resistor - 1%")
      (fields
        (field (name "MANUFACTURER PART NUMBER") "R0402_200R_1%_0.0625W_100PPM")
        (field (name "MANUFACTURER") "GENERIC")
        (field (name "AUTHOR") "CERN DEM JLC")
      )
      (libsource (lib "Resistors") (part "Resistor - 1%"))
    )
    (comp (ref "R315")
      (value "49R9")
      (footprint "RESC1005X40N")
      (description "Resistor - 1%")
      (fields
        (field (name "MANUFACTURER PART NUMBER") "R0402_49R9_1%_0.0625W_100PPM")
        (field (name "MANUFACTURER") "GENERIC")
        (field (name "AUTHOR") "CERN DEM JLC")
      )
      (libsource (lib "Resistors") (part "Resistor - 1%"))
    )
    (comp (ref "R316")
      (value "200")
      (footprint "RESC1005X40N")
      (description "Resistor - 1%")
      (fields
        (field (name "MANUFACTURER PART NUMBER") "R0402_200R_1%_0.0625W_100PPM")
        (field (name "MANUFACTURER") "GENERIC")
        (field (name "AUTHOR") "CERN DEM JLC")
      )
      (libsource (lib "Resistors") (part "Resistor - 1%"))
    )
    (comp (ref "R317")
      (value "200")
      (footprint "RESC1005X40N")
      (description "Resistor - 1%")
      (fields
        (field (name "MANUFACTURER PART NUMBER") "R0402_200R_1%_0.0625W_100PPM")
        (field (name "MANUFACTURER") "GENERIC")
        (field (name "AUTHOR") "CERN DEM JLC")
      )
      (libsource (lib "Resistors") (part "Resistor - 1%"))
    )
    (comp (ref "R318")
      (value "200")
      (footprint "RESC1005X40N")
      (description "Resistor - 1%")
      (fields
        (field (name "MANUFACTURER PART NUMBER") "R0402_200R_1%_0.0625W_100PPM")
        (field (name "MANUFACTURER") "GENERIC")
        (field (name "AUTHOR") "CERN DEM JLC")
      )
      (libsource (lib "Resistors") (part "Resistor - 1%"))
    )
    (comp (ref "R319")
      (value "200")
      (footprint "RESC1005X40N")
      (description "Resistor - 1%")
      (fields
        (field (name "MANUFACTURER PART NUMBER") "R0402_200R_1%_0.0625W_100PPM")
        (field (name "MANUFACTURER") "GENERIC")
        (field (name "AUTHOR") "CERN DEM JLC")
      )
      (libsource (lib "Resistors") (part "Resistor - 1%"))
    )
    (comp (ref "R320")
      (value "4k7")
      (footprint "RESC1005X40N")
      (description "Resistor - 1%")
      (fields
        (field (name "MANUFACTURER PART NUMBER") "R0402_4K7_1%_0.0625W_100PPM")
        (field (name "MANUFACTURER") "GENERIC")
        (field (name "AUTHOR") "CERN DEM JLC")
      )
      (libsource (lib "Resistors") (part "Resistor - 1%"))
    )
    (comp (ref "R321")
      (value "200")
      (footprint "RESC1005X40N")
      (description "Resistor - 1%")
      (fields
        (field (name "PART NUMBER") "R0402_200R_1%_0.0625W_100PPM")
        (field (name "POWER") "0.0625W")
        (field (name "AUTHOR") "CERN DEM JLC")
      )
      (libsource (lib "Resistors") (part "Resistor - 1%"))
    )
    (comp (ref "R322")
      (value "4k7")
      (footprint "RESC1005X40N")
      (description "Resistor - 1%")
      (fields
        (field (name "PART NUMBER") "R0402_4K7_1%_0.0625W_100PPM")
        (field (name "POWER") "0.0625W")
        (field (name "AUTHOR") "CERN DEM JLC")
      )
      (libsource (lib "Resistors") (part "Resistor - 1%"))
    )
    (comp (ref "R325")
      (value "4k7")
      (footprint "RESC1005X40N")
      (description "Resistor - 1%")
      (fields
        (field (name "PART NUMBER") "R0402_4K7_1%_0.0625W_100PPM")
        (field (name "POWER") "0.0625W")
        (field (name "AUTHOR") "CERN DEM JLC")
      )
      (libsource (lib "Resistors") (part "Resistor - 1%"))
    )
    (comp (ref "R367")
      (value "0")
      (footprint "RESC1005X40N")
      (description "Resistor")
      (fields
        (field (name "PART NUMBER") "R0402_0R_JUMPER")
        (field (name "MANUFACTURER") "GENERIC")
        (field (name "AUTHOR") "CERN DEM JLC")
      )
      (libsource (lib "Resistors") (part "Resistor"))
    )
    (comp (ref "R368")
      (value "49R9")
      (footprint "RESC1005X40N")
      (description "Resistor - 1%")
      (fields
        (field (name "MANUFACTURER PART NUMBER") "R0402_49R9_1%_0.0625W_100PPM")
        (field (name "MANUFACTURER") "GENERIC")
        (field (name "AUTHOR") "CERN DEM JLC")
      )
      (libsource (lib "Resistors") (part "Resistor - 1%"))
    )
    (comp (ref "R372")
      (value "200")
      (footprint "RESC1005X40N")
      (description "Resistor - 1%")
      (fields
        (field (name "PART NUMBER") "R0402_200R_1%_0.0625W_100PPM")
        (field (name "POWER") "0.0625W")
        (field (name "AUTHOR") "CERN DEM JLC")
      )
      (libsource (lib "Resistors") (part "Resistor - 1%"))
    )
    (comp (ref "R377")
      (value "200")
      (footprint "RESC1005X40N")
      (description "Resistor - 1%")
      (fields
        (field (name "PART NUMBER") "R0402_200R_1%_0.0625W_100PPM")
        (field (name "POWER") "0.0625W")
        (field (name "AUTHOR") "CERN DEM JLC")
      )
      (libsource (lib "Resistors") (part "Resistor - 1%"))
    )
    (comp (ref "R383")
      (value "0")
      (footprint "RESC1005X40N")
      (description "Resistor")
      (fields
        (field (name "PART NUMBER") "R0402_0R_JUMPER")
        (field (name "MANUFACTURER") "GENERIC")
        (field (name "AUTHOR") "CERN DEM JLC")
      )
      (libsource (lib "Resistors") (part "Resistor"))
    )
    (comp (ref "R386")
      (value "200")
      (footprint "RESC1005X40N")
      (description "Resistor - 1%")
      (fields
        (field (name "PART NUMBER") "R0402_200R_1%_0.0625W_100PPM")
        (field (name "POWER") "0.0625W")
        (field (name "AUTHOR") "CERN DEM JLC")
      )
      (libsource (lib "Resistors") (part "Resistor - 1%"))
    )
    (comp (ref "R389")
      (value "0")
      (footprint "RESC1005X40N")
      (description "Resistor")
      (fields
        (field (name "MANUFACTURER PART NUMBER") "R0402_0R_JUMPER")
        (field (name "MANUFACTURER") "GENERIC")
        (field (name "AUTHOR") "CERN DEM JLC")
      )
      (libsource (lib "Resistors") (part "Resistor"))
    )
    (comp (ref "R392")
      (value "0")
      (footprint "RESC1005X40N")
      (description "Resistor")
      (fields
        (field (name "PART NUMBER") "R0402_0R_JUMPER")
        (field (name "MANUFACTURER") "GENERIC")
        (field (name "AUTHOR") "CERN DEM JLC")
      )
      (libsource (lib "Resistors") (part "Resistor"))
    )
    (comp (ref "R394")
      (value "4k7")
      (footprint "RESC1005X40N")
      (description "Resistor - 1%")
      (fields
        (field (name "PART NUMBER") "R0402_4K7_1%_0.0625W_100PPM")
        (field (name "POWER") "0.0625W")
        (field (name "AUTHOR") "CERN DEM JLC")
      )
      (libsource (lib "Resistors") (part "Resistor - 1%"))
    )
    (comp (ref "R395")
      (value "4k7")
      (footprint "RESC1005X40N")
      (description "Resistor - 1%")
      (fields
        (field (name "PART NUMBER") "R0402_4K7_1%_0.0625W_100PPM")
        (field (name "POWER") "0.0625W")
        (field (name "AUTHOR") "CERN DEM JLC")
      )
      (libsource (lib "Resistors") (part "Resistor - 1%"))
    )
    (comp (ref "R396")
      (value "0")
      (footprint "RESC1005X40N")
      (description "Resistor")
      (fields
        (field (name "PART NUMBER") "R0402_0R_JUMPER")
        (field (name "MANUFACTURER") "GENERIC")
        (field (name "AUTHOR") "CERN DEM JLC")
      )
      (libsource (lib "Resistors") (part "Resistor"))
    )
    (comp (ref "R397")
      (value "0")
      (footprint "RESC1005X40N")
      (description "Resistor")
      (fields
        (field (name "PART NUMBER") "R0402_0R_JUMPER")
        (field (name "MANUFACTURER") "GENERIC")
        (field (name "AUTHOR") "CERN DEM JLC")
      )
      (libsource (lib "Resistors") (part "Resistor"))
    )
    (comp (ref "R399")
      (value "200")
      (footprint "RESC1005X40N")
      (description "Resistor - 1%")
      (fields
        (field (name "PART NUMBER") "R0402_200R_1%_0.0625W_100PPM")
        (field (name "POWER") "0.0625W")
        (field (name "AUTHOR") "CERN DEM JLC")
      )
      (libsource (lib "Resistors") (part "Resistor - 1%"))
    )
    (comp (ref "R400")
      (value "200")
      (footprint "RESC1005X40N")
      (description "Resistor - 1%")
      (fields
        (field (name "PART NUMBER") "R0402_200R_1%_0.0625W_100PPM")
        (field (name "POWER") "0.0625W")
        (field (name "AUTHOR") "CERN DEM JLC")
      )
      (libsource (lib "Resistors") (part "Resistor - 1%"))
    )
    (comp (ref "R401")
      (value "0")
      (footprint "RESC1005X40N")
      (description "Resistor")
      (fields
        (field (name "PART NUMBER") "R0402_0R_JUMPER")
        (field (name "MANUFACTURER") "GENERIC")
        (field (name "AUTHOR") "CERN DEM JLC")
      )
      (libsource (lib "Resistors") (part "Resistor"))
    )
    (comp (ref "R402")
      (value "0")
      (footprint "RESC1005X40N")
      (description "Resistor")
      (fields
        (field (name "PART NUMBER") "R0402_0R_JUMPER")
        (field (name "MANUFACTURER") "GENERIC")
        (field (name "AUTHOR") "CERN DEM JLC")
      )
      (libsource (lib "Resistors") (part "Resistor"))
    )
    (comp (ref "TP27")
      (value "Test Point")
      (footprint "TPS127")
      (fields (field (name "PART NUMBER") "SMD_PAD_1.27X1.27MM") (field (name "AUTHOR") "CERN DEM JLC"))
      (libsource (lib "Eletro-mechanical") (part "Test Point"))
    )
    (comp (ref "TP28")
      (value "Test Point")
      (footprint "TPS127")
      (fields (field (name "PART NUMBER") "SMD_PAD_1.27X1.27MM") (field (name "AUTHOR") "CERN DEM JLC"))
      (libsource (lib "Eletro-mechanical") (part "Test Point"))
    )
    (comp (ref "TP34")
      (value "Test Point")
      (footprint "TPS127")
      (fields (field (name "PART NUMBER") "SMD_PAD_1.27X1.27MM") (field (name "AUTHOR") "CERN DEM JLC"))
      (libsource (lib "Eletro-mechanical") (part "Test Point"))
    )
    (comp (ref "TP35")
      (value "Test Point")
      (footprint "TPS127")
      (fields (field (name "PART NUMBER") "SMD_PAD_1.27X1.27MM") (field (name "AUTHOR") "CERN DEM JLC"))
      (libsource (lib "Eletro-mechanical") (part "Test Point"))
    )
    (comp (ref "TP38")
      (value "Test Point")
      (footprint "TPS127")
      (fields (field (name "PART NUMBER") "SMD_PAD_1.27X1.27MM") (field (name "AUTHOR") "CERN DEM JLC"))
      (libsource (lib "Eletro-mechanical") (part "Test Point"))
    )
    (comp (ref "TP39")
      (value "Test Point")
      (footprint "TPS127")
      (fields (field (name "PART NUMBER") "SMD_PAD_1.27X1.27MM") (field (name "AUTHOR") "CERN DEM JLC"))
      (libsource (lib "Eletro-mechanical") (part "Test Point"))
    )
    (comp (ref "TP40")
      (value "Test Point")
      (footprint "TPS127")
      (fields (field (name "PART NUMBER") "SMD_PAD_1.27X1.27MM") (field (name "AUTHOR") "CERN DEM JLC"))
      (libsource (lib "Eletro-mechanical") (part "Test Point"))
    )
    (comp (ref "TP41")
      (value "Test Point")
      (footprint "TPS127")
      (fields (field (name "PART NUMBER") "SMD_PAD_1.27X1.27MM") (field (name "AUTHOR") "CERN DEM JLC"))
      (libsource (lib "Eletro-mechanical") (part "Test Point"))
    )
  )
  (nets
    (net (code "8") (name "/AUX_CLOCK_2_N") (class "Default")
      (node (ref "C495") (pin "1") (pinfunction "1_1") (pintype "passive"))
      (node (ref "IC52") (pin "13") (pinfunction "CKIN2-_13") (pintype "input"))
    )
    (net (code "9") (name "/AUX_CLOCK_2_P") (class "Default")
      (node (ref "C489") (pin "1") (pinfunction "1_1") (pintype "passive"))
      (node (ref "IC52") (pin "12") (pinfunction "CKIN2+_12") (pintype "input"))
    )
    (net (code "10") (name "/AUX_CLOCK_C2_N") (class "Default")
      (node (ref "C495") (pin "2") (pinfunction "2_2") (pintype "passive"))
      (node (ref "J10") (pin "1") (pinfunction "1_1") (pintype "bidirectional"))
      (node (ref "R306") (pin "1") (pinfunction "1_1") (pintype "passive"))
    )
    (net (code "11") (name "/AUX_CLOCK_C2_P") (class "Default")
      (node (ref "C489") (pin "2") (pinfunction "2_2") (pintype "passive"))
      (node (ref "J9") (pin "1") (pinfunction "1_1") (pintype "bidirectional"))
      (node (ref "R306") (pin "2") (pinfunction "2_2") (pintype "passive"))
    )
    (net (code "12") (name "/CDR_CLK_CLEAN0_N") (class "Default")
      (node (ref "C484") (pin "1") (pinfunction "1_1") (pintype "passive"))
    )
    (net (code "13") (name "/CDR_CLK_CLEAN0_P") (class "Default")
      (node (ref "C483") (pin "1") (pinfunction "1_1") (pintype "passive"))
    )
    (net (code "14") (name "/CDR_CLK_CLEAN1_N") (class "Default")
      (node (ref "C493") (pin "1") (pinfunction "1_1") (pintype "passive"))
    )
    (net (code "15") (name "/CDR_CLK_CLEAN1_P") (class "Default")
      (node (ref "C492") (pin "1") (pinfunction "1_1") (pintype "passive"))
    )
    (net (code "16") (name "/CDR_CLK_CLEAN2_N") (class "Default")
      (node (ref "C500") (pin "1") (pinfunction "1_1") (pintype "passive"))
    )
    (net (code "17") (name "/CDR_CLK_CLEAN2_P") (class "Default")
      (node (ref "C499") (pin "1") (pinfunction "1_1") (pintype "passive"))
    )
    (net (code "18") (name "/CDR_CLK_CLEAN3_N") (class "Default")
      (node (ref "C502") (pin "1") (pinfunction "1_1") (pintype "passive"))
    )
    (net (code "19") (name "/CDR_CLK_CLEAN3_P") (class "Default")
      (node (ref "C501") (pin "1") (pinfunction "1_1") (pintype "passive"))
    )
    (net (code "20") (name "/CDR_CLK_CLEAN4_N") (class "Default")
      (node (ref "C511") (pin "1") (pinfunction "1_1") (pintype "passive"))
    )
    (net (code "21") (name "/CDR_CLK_CLEAN4_P") (class "Default")
      (node (ref "C510") (pin "1") (pinfunction "1_1") (pintype "passive"))
    )
    (net (code "22") (name "/CKOUT1_B_N") (class "Default")
      (node (ref "C491") (pin "2") (pinfunction "2_2") (pintype "passive"))
      (node (ref "C494") (pin "2") (pinfunction "2_2") (pintype "passive"))
      (node (ref "IC45") (pin "6") (pinfunction "~{CLK1}_6") (pintype "input"))
    )
    (net (code "23") (name "/CKOUT1_B_P") (class "Default")
      (node (ref "C486") (pin "2") (pinfunction "2_2") (pintype "passive"))
      (node (ref "C490") (pin "2") (pinfunction "2_2") (pintype "passive"))
      (node (ref "IC45") (pin "5") (pinfunction "CLK1_5") (pintype "input"))
    )
    (net (code "24") (name "/CKOUT1_N") (class "Default")
      (node (ref "C491") (pin "1") (pinfunction "1_1") (pintype "passive"))
      (node (ref "IC52") (pin "34") (pinfunction "CKOUT2-_34") (pintype "output"))
      (node (ref "TP28") (pin "1") (pinfunction "1_1") (pintype "bidirectional"))
    )
    (net (code "25") (name "/CKOUT1_P") (class "Default")
      (node (ref "C490") (pin "1") (pinfunction "1_1") (pintype "passive"))
      (node (ref "IC52") (pin "35") (pinfunction "CKOUT2+_35") (pintype "output"))
      (node (ref "TP27") (pin "1") (pinfunction "1_1") (pintype "bidirectional"))
    )
    (net (code "26") (name "/CLEAN4_N") (class "Default")
      (node (ref "C511") (pin "2") (pinfunction "2_2") (pintype "passive"))
      (node (ref "IC45") (pin "11") (pinfunction "~{Q7}_11") (pintype "output"))
      (node (ref "R319") (pin "1") (pinfunction "1_1") (pintype "passive"))
    )
    (net (code "27") (name "/CLEAN4_P") (class "Default")
      (node (ref "C510") (pin "2") (pinfunction "2_2") (pintype "passive"))
      (node (ref "IC45") (pin "12") (pinfunction "Q7_12") (pintype "output"))
      (node (ref "R318") (pin "1") (pinfunction "1_1") (pintype "passive"))
    )
    (net (code "28") (name "/CLK_SEL") (class "Default")
      (node (ref "IC45") (pin "32") (pinfunction "IN_SEL_32") (pintype "input"))
    )
    (net (code "33") (name "/EN_P3V3_CLK") (class "Default")
      (node (ref "IC53") (pin "1") (pinfunction "EN_1") (pintype "power_in"))
    )
    (net (code "34") (name "/Helper_DCXO_N") (class "Default")
      (node (ref "C698") (pin "2") (pinfunction "2_2") (pintype "passive"))
      (node (ref "R401") (pin "2") (pinfunction "2_2") (pintype "passive"))
    )
    (net (code "35") (name "/Helper_DCXO_OE") (class "Default")
      (node (ref "R396") (pin "1") (pinfunction "1_1") (pintype "passive"))
      (node (ref "R402") (pin "1") (pinfunction "1_1") (pintype "passive"))
    )
    (net (code "36") (name "/Helper_DCXO_P") (class "Default")
      (node (ref "C697") (pin "2") (pinfunction "2_2") (pintype "passive"))
      (node (ref "R389") (pin "2") (pinfunction "2_2") (pintype "passive"))
      (node (ref "R392") (pin "2") (pinfunction "2_2") (pintype "passive"))
    )
    (net (code "37") (name "/Helper_DCXO_SCL") (class "Default")
      (node (ref "OSC2") (pin "8") (pinfunction "SCL_8") (pintype "input"))
      (node (ref "R394") (pin "1") (pinfunction "1_1") (pintype "passive"))
      (node (ref "TP41") (pin "1") (pinfunction "1_1") (pintype "bidirectional"))
    )
    (net (code "38") (name "/Helper_DCXO_SDA") (class "Default")
      (node (ref "OSC2") (pin "7") (pinfunction "SDA_7") (pintype "bidirectional"))
      (node (ref "R395") (pin "1") (pinfunction "1_1") (pintype "passive"))
      (node (ref "TP40") (pin "1") (pinfunction "1_1") (pintype "bidirectional"))
    )
    (net (code "40") (name "/Main_DCXO_N") (class "Default")
      (node (ref "C594") (pin "2") (pinfunction "2_2") (pintype "passive"))
      (node (ref "C639") (pin "2") (pinfunction "2_2") (pintype "passive"))
      (node (ref "IC45") (pin "2") (pinfunction "~{CLK0}_2") (pintype "input"))
    )
    (net (code "41") (name "/Main_DCXO_OE") (class "Default")
      (node (ref "R367") (pin "1") (pinfunction "1_1") (pintype "passive"))
      (node (ref "R383") (pin "1") (pinfunction "1_1") (pintype "passive"))
    )
    (net (code "42") (name "/Main_DCXO_P") (class "Default")
      (node (ref "C592") (pin "2") (pinfunction "2_2") (pintype "passive"))
      (node (ref "IC45") (pin "1") (pinfunction "CLK0_1") (pintype "input"))
    )
    (net (code "43") (name "/Main_DCXO_SCL") (class "Default")
      (node (ref "OSC1") (pin "8") (pinfunction "SCL_8") (pintype "input"))
      (node (ref "R322") (pin "1") (pinfunction "1_1") (pintype "passive"))
      (node (ref "TP39") (pin "1") (pinfunction "1_1") (pintype "bidirectional"))
    )
    (net (code "44") (name "/Main_DCXO_SDA") (class "Default")
      (node (ref "OSC1") (pin "7") (pinfunction "SDA_7") (pintype "bidirectional"))
      (node (ref "R325") (pin "1") (pinfunction "1_1") (pintype "passive"))
      (node (ref "TP38") (pin "1") (pinfunction "1_1") (pintype "bidirectional"))
    )
    (net (code "45") (name "/OUT_N") (class "Default")
      (node (ref "C482") (pin "2") (pinfunction "2_2") (pintype "passive"))
      (node (ref "IC45") (pin "29") (pinfunction "~{Q0}_29") (pintype "output"))
      (node (ref "R290") (pin "1") (pinfunction "1_1") (pintype "passive"))
    )
    (net (code "46") (name "/OUT_P") (class "Default")
      (node (ref "C159") (pin "2") (pinfunction "2_2") (pintype "passive"))
      (node (ref "IC45") (pin "30") (pinfunction "Q0_30") (pintype "output"))
      (node (ref "R288") (pin "1") (pinfunction "1_1") (pintype "passive"))
    )
    (net (code "47") (name "/P5V0_LDO_IN") (class "Default")
      (node (ref "C519") (pin "2") (pinfunction "2_2") (pintype "passive"))
      (node (ref "IC53") (pin "2") (pinfunction "IN_2") (pintype "input"))
      (node (ref "L38") (pin "2") (pinfunction "2_2") (pintype "passive"))
    )
    (net (code "48") (name "/REC_CLOCK") (class "Default")
      (node (ref "R289") (pin "1") (pinfunction "1_1") (pintype "passive"))
    )
    (net (code "49") (name "/REC_CLOCK_C") (class "Default")
      (node (ref "C158") (pin "2") (pinfunction "2_2") (pintype "passive"))
      (node (ref "R287") (pin "1") (pinfunction "1_1") (pintype "passive"))
      (node (ref "R289") (pin "2") (pinfunction "2_2") (pintype "passive"))
      (node (ref "R293") (pin "2") (pinfunction "2_2") (pintype "passive"))
    )
    (net (code "50") (name "/REC_CLOCK_N") (class "Default")
      (node (ref "C485") (pin "1") (pinfunction "1_1") (pintype "passive"))
      (node (ref "IC52") (pin "17") (pinfunction "CKIN1-_17") (pintype "input"))
    )
    (net (code "51") (name "/REC_CLOCK_P") (class "Default")
      (node (ref "C158") (pin "1") (pinfunction "1_1") (pintype "passive"))
      (node (ref "IC52") (pin "16") (pinfunction "CKIN1+_16") (pintype "input"))
    )
    (net (code "52") (name "/RF_OUT") (class "Default")
      (node (ref "C488") (pin "2") (pinfunction "2_2") (pintype "passive"))
    )
    (net (code "53") (name "/SI5324_RST") (class "Default")
      (node (ref "IC52") (pin "1") (pinfunction "~{RST}_1") (pintype "input"))
    )
    (net (code "54") (name "/SI5324_SCL") (class "Default")
      (node (ref "IC52") (pin "22") (pinfunction "SCL_22") (pintype "input"))
      (node (ref "TP35") (pin "1") (pinfunction "1_1") (pintype "bidirectional"))
    )
    (net (code "55") (name "/SI5324_SDA") (class "Default")
      (node (ref "IC52") (pin "23") (pinfunction "SDA_SDO_23") (pintype "bidirectional"))
      (node (ref "TP34") (pin "1") (pinfunction "1_1") (pintype "bidirectional"))
    )
    (net (code "56") (name "/SI5324_VDD") (class "Default")
      (node (ref "C513") (pin "2") (pinfunction "2_2") (pintype "passive"))
      (node (ref "C514") (pin "2") (pinfunction "2_2") (pintype "passive"))
      (node (ref "C515") (pin "2") (pinfunction "2_2") (pintype "passive"))
      (node (ref "C516") (pin "1") (pinfunction "1_1") (pintype "passive"))
      (node (ref "IC52") (pin "10") (pinfunction "VDD_10") (pintype "power_in"))
      (node (ref "IC52") (pin "32") (pinfunction "VDD_32") (pintype "power_in"))
      (node (ref "IC52") (pin "5") (pinfunction "VDD_5") (pintype "power_in"))
      (node (ref "L37") (pin "2") (pinfunction "2_2") (pintype "passive"))
    )
    (net (code "57") (name "/SI5328_XTAL_XA") (class "Default")
      (node (ref "IC52") (pin "6") (pinfunction "XA_6") (pintype "input"))
      (node (ref "Q2") (pin "3") (pinfunction "X_3") (pintype "passive"))
    )
    (net (code "58") (name "/SI5328_XTAL_XB") (class "Default")
      (node (ref "IC52") (pin "7") (pinfunction "XB_7") (pintype "input"))
      (node (ref "Q2") (pin "1") (pinfunction "X_1") (pintype "passive"))
    )
    (net (code "59") (name "/TCLKA_N") (class "Default")
      (node (ref "C494") (pin "1") (pinfunction "1_1") (pintype "passive"))
    )
    (net (code "60") (name "/TCLKA_P") (class "Default")
      (node (ref "C486") (pin "1") (pinfunction "1_1") (pintype "passive"))
    )
    (net (code "61") (name "/TCLKB_N") (class "Default")
      (node (ref "C517") (pin "1") (pinfunction "1_1") (pintype "passive"))
    )
    (net (code "62") (name "/TCLKB_P") (class "Default")
      (node (ref "C518") (pin "1") (pinfunction "1_1") (pintype "passive"))
    )
    (net (code "63") (name "/TCLK_B_N") (class "Default")
      (node (ref "C517") (pin "2") (pinfunction "2_2") (pintype "passive"))
      (node (ref "J13") (pin "1") (pinfunction "1_1") (pintype "bidirectional"))
    )
    (net (code "64") (name "/TCLK_B_P") (class "Default")
      (node (ref "C518") (pin "2") (pinfunction "2_2") (pintype "passive"))
      (node (ref "J15") (pin "1") (pinfunction "1_1") (pintype "bidirectional"))
    )
    (net (code "69") (name "GND") (class "Default")
      (node (ref "C485") (pin "2") (pinfunction "2_2") (pintype "passive"))
      (node (ref "C487") (pin "1") (pinfunction "1_1") (pintype "passive"))
      (node (ref "C496") (pin "1") (pinfunction "1_1") (pintype "passive"))
      (node (ref "C503") (pin "1") (pinfunction "1_1") (pintype "passive"))
      (node (ref "C504") (pin "1") (pinfunction "1_1") (pintype "passive"))
      (node (ref "C505") (pin "1") (pinfunction "1_1") (pintype "passive"))
      (node (ref "C506") (pin "1") (pinfunction "1_1") (pintype "passive"))
      (node (ref "C507") (pin "1") (pinfunction "1_1") (pintype "passive"))
      (node (ref "C508") (pin "1") (pinfunction "1_1") (pintype "passive"))
      (node (ref "C509") (pin "1") (pinfunction "1_1") (pintype "passive"))
      (node (ref "C512") (pin "1") (pinfunction "1_1") (pintype "passive"))
      (node (ref "C513") (pin "1") (pinfunction "1_1") (pintype "passive"))
      (node (ref "C514") (pin "1") (pinfunction "1_1") (pintype "passive"))
      (node (ref "C515") (pin "1") (pinfunction "1_1") (pintype "passive"))
      (node (ref "C516") (pin "2") (pinfunction "2_2") (pintype "passive"))
      (node (ref "C519") (pin "1") (pinfunction "1_1") (pintype "passive"))
      (node (ref "C520") (pin "1") (pinfunction "1_1") (pintype "passive"))
      (node (ref "C521") (pin "1") (pinfunction "1_1") (pintype "passive"))
      (node (ref "C522") (pin "1") (pinfunction "1_1") (pintype "passive"))
      (node (ref "C590") (pin "1") (pinfunction "1_1") (pintype "passive"))
      (node (ref "C591") (pin "1") (pinfunction "1_1") (pintype "passive"))
      (node (ref "C595") (pin "1") (pinfunction "1_1") (pintype "passive"))
      (node (ref "C639") (pin "1") (pinfunction "1_1") (pintype "passive"))
      (node (ref "C640") (pin "1") (pinfunction "1_1") (pintype "passive"))
      (node (ref "C641") (pin "1") (pinfunction "1_1") (pintype "passive"))
      (node (ref "C642") (pin "1") (pinfunction "1_1") (pintype "passive"))
      (node (ref "C699") (pin "1") (pinfunction "1_1") (pintype "passive"))
      (node (ref "IC45") (pin "33") (pinfunction "VEE_33") (pintype "power_in"))
      (node (ref "IC52") (pin "19") (pinfunction "GND_19") (pintype "power_in"))
      (node (ref "IC52") (pin "20") (pinfunction "GND_20") (pintype "power_in"))
      (node (ref "IC52") (pin "24") (pinfunction "A0_24") (pintype "input"))
      (node (ref "IC52") (pin "25") (pinfunction "A1_25") (pintype "input"))
      (node (ref "IC52") (pin "26") (pinfunction "A2_~{SS}_26") (pintype "input"))
      (node (ref "IC52") (pin "31") (pinfunction "GND_31") (pintype "power_in"))
      (node (ref "IC52") (pin "36") (pinfunction "CMODE_36") (pintype "input"))
      (node (ref "IC52") (pin "37") (pinfunction "GND_37") (pintype "power_in"))
      (node (ref "IC52") (pin "8") (pinfunction "GND_8") (pintype "power_in"))
      (node (ref "IC53") (pin "3") (pinfunction "GND_3") (pintype "power_in"))
      (node (ref "IC53") (pin "6") (pinfunction "GND_6") (pintype "power_in"))
      (node (ref "J10") (pin "2") (pinfunction "2_2") (pintype "bidirectional"))
      (node (ref "J13") (pin "2") (pinfunction "2_2") (pintype "bidirectional"))
      (node (ref "J15") (pin "2") (pinfunction "2_2") (pintype "bidirectional"))
      (node (ref "J16") (pin "2") (pinfunction "2_2") (pintype "bidirectional"))
      (node (ref "J4") (pin "2") (pinfunction "2_2") (pintype "bidirectional"))
      (node (ref "J5") (pin "2") (pinfunction "2_2") (pintype "bidirectional"))
      (node (ref "J9") (pin "2") (pinfunction "2_2") (pintype "bidirectional"))
      (node (ref "OSC1") (pin "3") (pinfunction "GND_3") (pintype "power_in"))
      (node (ref "OSC2") (pin "3") (pinfunction "GND_3") (pintype "power_in"))
      (node (ref "Q2") (pin "2") (pinfunction "GND_2") (pintype "power_in"))
      (node (ref "Q2") (pin "4") (pinfunction "GND_4") (pintype "power_in"))
      (node (ref "R288") (pin "2") (pinfunction "2_2") (pintype "passive"))
      (node (ref "R290") (pin "2") (pinfunction "2_2") (pintype "passive"))
      (node (ref "R293") (pin "1") (pinfunction "1_1") (pintype "passive"))
      (node (ref "R294") (pin "2") (pinfunction "2_2") (pintype "passive"))
      (node (ref "R296") (pin "2") (pinfunction "2_2") (pintype "passive"))
      (node (ref "R299") (pin "2") (pinfunction "2_2") (pintype "passive"))
      (node (ref "R300") (pin "2") (pinfunction "2_2") (pintype "passive"))
      (node (ref "R301") (pin "2") (pinfunction "2_2") (pintype "passive"))
      (node (ref "R303") (pin "2") (pinfunction "2_2") (pintype "passive"))
      (node (ref "R307") (pin "2") (pinfunction "2_2") (pintype "passive"))
      (node (ref "R309") (pin "2") (pinfunction "2_2") (pintype "passive"))
      (node (ref "R311") (pin "2") (pinfunction "2_2") (pintype "passive"))
      (node (ref "R314") (pin "2") (pinfunction "2_2") (pintype "passive"))
      (node (ref "R316") (pin "2") (pinfunction "2_2") (pintype "passive"))
      (node (ref "R317") (pin "2") (pinfunction "2_2") (pintype "passive"))
      (node (ref "R318") (pin "2") (pinfunction "2_2") (pintype "passive"))
      (node (ref "R319") (pin "2") (pinfunction "2_2") (pintype "passive"))
      (node (ref "R320") (pin "1") (pinfunction "1_1") (pintype "passive"))
      (node (ref "R372") (pin "1") (pinfunction "1_1") (pintype "passive"))
      (node (ref "R377") (pin "1") (pinfunction "1_1") (pintype "passive"))
      (node (ref "R399") (pin "1") (pinfunction "1_1") (pintype "passive"))
      (node (ref "R400") (pin "1") (pinfunction "1_1") (pintype "passive"))
      (node (ref "R401") (pin "1") (pinfunction "1_1") (pintype "passive"))
    )
    (net (code "70") (name "Net-(C159-Pad1)") (class "Default")
      (node (ref "C159") (pin "1") (pinfunction "1_1") (pintype "passive"))
      (node (ref "J4") (pin "1") (pinfunction "1_1") (pintype "bidirectional"))
    )
    (net (code "71") (name "Net-(C482-Pad1)") (class "Default")
      (node (ref "C482") (pin "1") (pinfunction "1_1") (pintype "passive"))
      (node (ref "J5") (pin "1") (pinfunction "1_1") (pintype "bidirectional"))
    )
    (net (code "72") (name "Net-(C483-Pad2)") (class "Default")
      (node (ref "C483") (pin "2") (pinfunction "2_2") (pintype "passive"))
      (node (ref "R295") (pin "2") (pinfunction "2_2") (pintype "passive"))
    )
    (net (code "73") (name "Net-(C484-Pad2)") (class "Default")
      (node (ref "C484") (pin "2") (pinfunction "2_2") (pintype "passive"))
      (node (ref "R297") (pin "2") (pinfunction "2_2") (pintype "passive"))
    )
    (net (code "74") (name "Net-(C492-Pad2)") (class "Default")
      (node (ref "C492") (pin "2") (pinfunction "2_2") (pintype "passive"))
      (node (ref "R302") (pin "2") (pinfunction "2_2") (pintype "passive"))
    )
    (net (code "75") (name "Net-(C493-Pad2)") (class "Default")
      (node (ref "C493") (pin "2") (pinfunction "2_2") (pintype "passive"))
      (node (ref "R304") (pin "2") (pinfunction "2_2") (pintype "passive"))
    )
    (net (code "76") (name "Net-(C497-Pad2)") (class "Default")
      (node (ref "C497") (pin "2") (pinfunction "2_2") (pintype "passive"))
      (node (ref "R308") (pin "2") (pinfunction "2_2") (pintype "passive"))
    )
    (net (code "77") (name "Net-(C498-Pad2)") (class "Default")
      (node (ref "C498") (pin "2") (pinfunction "2_2") (pintype "passive"))
      (node (ref "R310") (pin "2") (pinfunction "2_2") (pintype "passive"))
    )
    (net (code "78") (name "Net-(C499-Pad2)") (class "Default")
      (node (ref "C499") (pin "2") (pinfunction "2_2") (pintype "passive"))
      (node (ref "R312") (pin "2") (pinfunction "2_2") (pintype "passive"))
    )
    (net (code "79") (name "Net-(C500-Pad2)") (class "Default")
      (node (ref "C500") (pin "2") (pinfunction "2_2") (pintype "passive"))
      (node (ref "R315") (pin "2") (pinfunction "2_2") (pintype "passive"))
    )
    (net (code "80") (name "Net-(C522-Pad2)") (class "Default")
      (node (ref "C522") (pin "2") (pinfunction "2_2") (pintype "passive"))
      (node (ref "R321") (pin "1") (pinfunction "1_1") (pintype "passive"))
      (node (ref "R322") (pin "2") (pinfunction "2_2") (pintype "passive"))
      (node (ref "R325") (pin "2") (pinfunction "2_2") (pintype "passive"))
    )
    (net (code "81") (name "Net-(C592-Pad1)") (class "Default")
      (node (ref "C592") (pin "1") (pinfunction "1_1") (pintype "passive"))
      (node (ref "R368") (pin "2") (pinfunction "2_2") (pintype "passive"))
      (node (ref "R372") (pin "2") (pinfunction "2_2") (pintype "passive"))
    )
    (net (code "82") (name "Net-(C640-Pad2)") (class "Default")
      (node (ref "C640") (pin "2") (pinfunction "2_2") (pintype "passive"))
      (node (ref "R386") (pin "1") (pinfunction "1_1") (pintype "passive"))
      (node (ref "R394") (pin "2") (pinfunction "2_2") (pintype "passive"))
      (node (ref "R395") (pin "2") (pinfunction "2_2") (pintype "passive"))
    )
    (net (code "83") (name "Net-(C697-Pad1)") (class "Default")
      (node (ref "C697") (pin "1") (pinfunction "1_1") (pintype "passive"))
      (node (ref "R392") (pin "1") (pinfunction "1_1") (pintype "passive"))
      (node (ref "R397") (pin "2") (pinfunction "2_2") (pintype "passive"))
      (node (ref "R399") (pin "2") (pinfunction "2_2") (pintype "passive"))
    )
    (net (code "84") (name "Net-(IC45-Q1)") (class "Default")
      (node (ref "IC45") (pin "28") (pinfunction "Q1_28") (pintype "output"))
      (node (ref "R294") (pin "1") (pinfunction "1_1") (pintype "passive"))
      (node (ref "R295") (pin "1") (pinfunction "1_1") (pintype "passive"))
    )
    (net (code "85") (name "Net-(IC45-Q2)") (class "Default")
      (node (ref "C488") (pin "1") (pinfunction "1_1") (pintype "passive"))
      (node (ref "IC45") (pin "24") (pinfunction "Q2_24") (pintype "output"))
      (node (ref "R299") (pin "1") (pinfunction "1_1") (pintype "passive"))
    )
    (net (code "86") (name "Net-(IC45-Q3)") (class "Default")
      (node (ref "IC45") (pin "22") (pinfunction "Q3_22") (pintype "output"))
      (node (ref "R301") (pin "1") (pinfunction "1_1") (pintype "passive"))
      (node (ref "R302") (pin "1") (pinfunction "1_1") (pintype "passive"))
    )
    (net (code "87") (name "Net-(IC45-Q4)") (class "Default")
      (node (ref "IC45") (pin "20") (pinfunction "Q4_20") (pintype "output"))
      (node (ref "R307") (pin "1") (pinfunction "1_1") (pintype "passive"))
      (node (ref "R308") (pin "1") (pinfunction "1_1") (pintype "passive"))
    )
    (net (code "88") (name "Net-(IC45-Q5)") (class "Default")
      (node (ref "IC45") (pin "18") (pinfunction "Q5_18") (pintype "output"))
      (node (ref "R311") (pin "1") (pinfunction "1_1") (pintype "passive"))
      (node (ref "R312") (pin "1") (pinfunction "1_1") (pintype "passive"))
    )
    (net (code "89") (name "Net-(IC45-Q6)") (class "Default")
      (node (ref "C501") (pin "2") (pinfunction "2_2") (pintype "passive"))
      (node (ref "IC45") (pin "14") (pinfunction "Q6_14") (pintype "output"))
      (node (ref "R316") (pin "1") (pinfunction "1_1") (pintype "passive"))
    )
    (net (code "90") (name "Net-(IC45-VREF0)") (class "Default")
      (node (ref "IC45") (pin "3") (pinfunction "VREF0_3") (pintype "input"))
      (node (ref "R298") (pin "2") (pinfunction "2_2") (pintype "passive"))
    )
    (net (code "91") (name "Net-(IC45-VREF1)") (class "Default")
      (node (ref "IC45") (pin "8") (pinfunction "VREF1_8") (pintype "input"))
      (node (ref "R305") (pin "2") (pinfunction "2_2") (pintype "passive"))
    )
    (net (code "92") (name "Net-(IC45-VT0)") (class "Default")
      (node (ref "C487") (pin "2") (pinfunction "2_2") (pintype "passive"))
      (node (ref "IC45") (pin "4") (pinfunction "VT0_4") (pintype "passive"))
      (node (ref "R298") (pin "1") (pinfunction "1_1") (pintype "passive"))
    )
    (net (code "93") (name "Net-(IC45-VT1)") (class "Default")
      (node (ref "C496") (pin "2") (pinfunction "2_2") (pintype "passive"))
      (node (ref "IC45") (pin "7") (pinfunction "VT1_7") (pintype "passive"))
      (node (ref "R305") (pin "1") (pinfunction "1_1") (pintype "passive"))
    )
    (net (code "94") (name "Net-(IC45-~{Q1})") (class "Default")
      (node (ref "IC45") (pin "27") (pinfunction "~{Q1}_27") (pintype "output"))
      (node (ref "R296") (pin "1") (pinfunction "1_1") (pintype "passive"))
      (node (ref "R297") (pin "1") (pinfunction "1_1") (pintype "passive"))
    )
    (net (code "95") (name "Net-(IC45-~{Q2})") (class "Default")
      (node (ref "IC45") (pin "23") (pinfunction "~{Q2}_23") (pintype "output"))
      (node (ref "R300") (pin "1") (pinfunction "1_1") (pintype "passive"))
    )
    (net (code "96") (name "Net-(IC45-~{Q3})") (class "Default")
      (node (ref "IC45") (pin "21") (pinfunction "~{Q3}_21") (pintype "output"))
      (node (ref "R303") (pin "1") (pinfunction "1_1") (pintype "passive"))
      (node (ref "R304") (pin "1") (pinfunction "1_1") (pintype "passive"))
    )
    (net (code "97") (name "Net-(IC45-~{Q4})") (class "Default")
      (node (ref "IC45") (pin "19") (pinfunction "~{Q4}_19") (pintype "output"))
      (node (ref "R309") (pin "1") (pinfunction "1_1") (pintype "passive"))
      (node (ref "R310") (pin "1") (pinfunction "1_1") (pintype "passive"))
    )
    (net (code "98") (name "Net-(IC45-~{Q5})") (class "Default")
      (node (ref "IC45") (pin "17") (pinfunction "~{Q5}_17") (pintype "output"))
      (node (ref "R314") (pin "1") (pinfunction "1_1") (pintype "passive"))
      (node (ref "R315") (pin "1") (pinfunction "1_1") (pintype "passive"))
    )
    (net (code "99") (name "Net-(IC45-~{Q6})") (class "Default")
      (node (ref "C502") (pin "2") (pinfunction "2_2") (pintype "passive"))
      (node (ref "IC45") (pin "13") (pinfunction "~{Q6}_13") (pintype "output"))
      (node (ref "R317") (pin "1") (pinfunction "1_1") (pintype "passive"))
    )
    (net (code "100") (name "Net-(IC52-CS_CA)") (class "Default")
      (node (ref "IC52") (pin "21") (pinfunction "CS_CA_21") (pintype "bidirectional"))
      (node (ref "R320") (pin "2") (pinfunction "2_2") (pintype "passive"))
    )
    (net (code "101") (name "Net-(IC53-NR)") (class "Default")
      (node (ref "C521") (pin "2") (pinfunction "2_2") (pintype "passive"))
      (node (ref "IC53") (pin "5") (pinfunction "NR_5") (pintype "passive"))
    )
    (net (code "102") (name "Net-(J16-Pad1)") (class "Default")
      (node (ref "J16") (pin "1") (pinfunction "1_1") (pintype "bidirectional"))
      (node (ref "R389") (pin "1") (pinfunction "1_1") (pintype "passive"))
    )
    (net (code "103") (name "Net-(OSC1-CLK+)") (class "Default")
      (node (ref "OSC1") (pin "4") (pinfunction "CLK+_4") (pintype "output"))
      (node (ref "R368") (pin "1") (pinfunction "1_1") (pintype "passive"))
    )
    (net (code "104") (name "Net-(OSC1-CLK-)") (class "Default")
      (node (ref "C594") (pin "1") (pinfunction "1_1") (pintype "passive"))
      (node (ref "OSC1") (pin "5") (pinfunction "CLK-_5") (pintype "output"))
      (node (ref "R377") (pin "2") (pinfunction "2_2") (pintype "passive"))
    )
    (net (code "105") (name "Net-(OSC1-NC)") (class "Default")
      (node (ref "OSC1") (pin "2") (pinfunction "NC_2") (pintype "passive"))
      (node (ref "R383") (pin "2") (pinfunction "2_2") (pintype "passive"))
    )
    (net (code "106") (name "Net-(OSC1-OE)") (class "Default")
      (node (ref "OSC1") (pin "1") (pinfunction "OE_1") (pintype "input"))
      (node (ref "R367") (pin "2") (pinfunction "2_2") (pintype "passive"))
    )
    (net (code "107") (name "Net-(OSC1-VDD)") (class "Default")
      (node (ref "C590") (pin "2") (pinfunction "2_2") (pintype "passive"))
      (node (ref "C591") (pin "2") (pinfunction "2_2") (pintype "passive"))
      (node (ref "C595") (pin "2") (pinfunction "2_2") (pintype "passive"))
      (node (ref "L44") (pin "2") (pinfunction "2_2") (pintype "passive"))
      (node (ref "OSC1") (pin "6") (pinfunction "VDD_6") (pintype "power_in"))
    )
    (net (code "108") (name "Net-(OSC2-CLK+)") (class "Default")
      (node (ref "OSC2") (pin "4") (pinfunction "CLK+_4") (pintype "output"))
      (node (ref "R397") (pin "1") (pinfunction "1_1") (pintype "passive"))
    )
    (net (code "109") (name "Net-(OSC2-CLK-)") (class "Default")
      (node (ref "C698") (pin "1") (pinfunction "1_1") (pintype "passive"))
      (node (ref "OSC2") (pin "5") (pinfunction "CLK-_5") (pintype "output"))
      (node (ref "R400") (pin "2") (pinfunction "2_2") (pintype "passive"))
    )
    (net (code "110") (name "Net-(OSC2-NC)") (class "Default")
      (node (ref "OSC2") (pin "2") (pinfunction "NC_2") (pintype "passive"))
      (node (ref "R402") (pin "2") (pinfunction "2_2") (pintype "passive"))
    )
    (net (code "111") (name "Net-(OSC2-OE)") (class "Default")
      (node (ref "OSC2") (pin "1") (pinfunction "OE_1") (pintype "input"))
      (node (ref "R396") (pin "2") (pinfunction "2_2") (pintype "passive"))
    )
    (net (code "112") (name "Net-(OSC2-VDD)") (class "Default")
      (node (ref "C641") (pin "2") (pinfunction "2_2") (pintype "passive"))
      (node (ref "C642") (pin "2") (pinfunction "2_2") (pintype "passive"))
      (node (ref "C699") (pin "2") (pinfunction "2_2") (pintype "passive"))
      (node (ref "L60") (pin "2") (pinfunction "2_2") (pintype "passive"))
      (node (ref "OSC2") (pin "6") (pinfunction "VDD_6") (pintype "power_in"))
    )
    (net (code "113") (name "P3V3") (class "Default")
      (node (ref "R321") (pin "2") (pinfunction "2_2") (pintype "passive"))
      (node (ref "R386") (pin "2") (pinfunction "2_2") (pintype "passive"))
    )
    (net (code "114") (name "P3V3_CDR") (class "Default")
      (node (ref "C512") (pin "2") (pinfunction "2_2") (pintype "passive"))
      (node (ref "C520") (pin "2") (pinfunction "2_2") (pintype "passive"))
      (node (ref "IC53") (pin "4") (pinfunction "OUT_4") (pintype "power_in"))
      (node (ref "L36") (pin "2") (pinfunction "2_2") (pintype "passive"))
      (node (ref "L37") (pin "1") (pinfunction "1_1") (pintype "passive"))
      (node (ref "L44") (pin "1") (pinfunction "1_1") (pintype "passive"))
      (node (ref "L60") (pin "1") (pinfunction "1_1") (pintype "passive"))
      (node (ref "R287") (pin "2") (pinfunction "2_2") (pintype "passive"))
    )
    (net (code "115") (name "P3V3_CLKDIS3F") (class "Default")
      (node (ref "C503") (pin "2") (pinfunction "2_2") (pintype "passive"))
      (node (ref "C504") (pin "2") (pinfunction "2_2") (pintype "passive"))
      (node (ref "C505") (pin "2") (pinfunction "2_2") (pintype "passive"))
      (node (ref "C506") (pin "2") (pinfunction "2_2") (pintype "passive"))
      (node (ref "C507") (pin "2") (pinfunction "2_2") (pintype "passive"))
      (node (ref "C508") (pin "2") (pinfunction "2_2") (pintype "passive"))
      (node (ref "C509") (pin "2") (pinfunction "2_2") (pintype "passive"))
      (node (ref "IC45") (pin "10") (pinfunction "VCC_10") (pintype "power_in"))
      (node (ref "IC45") (pin "15") (pinfunction "VCC_15") (pintype "power_in"))
      (node (ref "IC45") (pin "16") (pinfunction "VCC_16") (pintype "power_in"))
      (node (ref "IC45") (pin "25") (pinfunction "VCC_25") (pintype "power_in"))
      (node (ref "IC45") (pin "26") (pinfunction "VCC_26") (pintype "power_in"))
      (node (ref "IC45") (pin "31") (pinfunction "VCC_31") (pintype "power_in"))
      (node (ref "L36") (pin "1") (pinfunction "1_1") (pintype "passive"))
    )
    (net (code "116") (name "P4V0") (class "Default")
      (node (ref "L38") (pin "1") (pinfunction "1_1") (pintype "passive"))
    )
    (net (code "117") (name "unconnected-(C497-Pad1)") (class "Default")
      (node (ref "C497") (pin "1") (pinfunction "1_1") (pintype "passive"))
    )
    (net (code "118") (name "unconnected-(C498-Pad1)") (class "Default")
      (node (ref "C498") (pin "1") (pinfunction "1_1") (pintype "passive"))
    )
    (net (code "119") (name "unconnected-(IC45-NC-Pad9)") (class "Default")
      (node (ref "IC45") (pin "9") (pinfunction "NC_9") (pintype "passive+no_connect"))
    )
    (net (code "120") (name "unconnected-(IC52-C2B-Pad4)") (class "Default")
      (node (ref "IC52") (pin "4") (pinfunction "C2B_4") (pintype "output+no_connect"))
    )
    (net (code "121") (name "unconnected-(IC52-CKOUT1+-Pad28)") (class "Default")
      (node (ref "IC52") (pin "28") (pinfunction "CKOUT1+_28") (pintype "output"))
    )
    (net (code "122") (name "unconnected-(IC52-CKOUT1--Pad29)") (class "Default")
      (node (ref "IC52") (pin "29") (pinfunction "CKOUT1-_29") (pintype "output"))
    )
    (net (code "123") (name "unconnected-(IC52-INT_C1B-Pad3)") (class "Default")
      (node (ref "IC52") (pin "3") (pinfunction "INT_C1B_3") (pintype "output+no_connect"))
    )
    (net (code "124") (name "unconnected-(IC52-LOL-Pad18)") (class "Default")
      (node (ref "IC52") (pin "18") (pinfunction "LOL_18") (pintype "output+no_connect"))
    )
    (net (code "125") (name "unconnected-(IC52-NC-Pad2)") (class "Default")
      (node (ref "IC52") (pin "2") (pinfunction "NC_2") (pintype "passive+no_connect"))
    )
    (net (code "126") (name "unconnected-(IC52-NC-Pad9)") (class "Default")
      (node (ref "IC52") (pin "9") (pinfunction "NC_9") (pintype "passive+no_connect"))
    )
    (net (code "127") (name "unconnected-(IC52-NC-Pad14)") (class "Default")
      (node (ref "IC52") (pin "14") (pinfunction "NC_14") (pintype "passive+no_connect"))
    )
    (net (code "128") (name "unconnected-(IC52-NC-Pad30)") (class "Default")
      (node (ref "IC52") (pin "30") (pinfunction "NC_30") (pintype "passive+no_connect"))
    )
    (net (code "129") (name "unconnected-(IC52-NC-Pad33)") (class "Default")
      (node (ref "IC52") (pin "33") (pinfunction "NC_33") (pintype "passive+no_connect"))
    )
    (net (code "130") (name "unconnected-(IC52-RATE0-Pad11)") (class "Default")
      (node (ref "IC52") (pin "11") (pinfunction "RATE0_11") (pintype "input+no_connect"))
    )
    (net (code "131") (name "unconnected-(IC52-RATE1-Pad15)") (class "Default")
      (node (ref "IC52") (pin "15") (pinfunction "RATE1_15") (pintype "input+no_connect"))
    )
    (net (code "132") (name "unconnected-(IC52-SDI-Pad27)") (class "Default")
      (node (ref "IC52") (pin "27") (pinfunction "SDI_27") (pintype "input+no_connect"))
    )
  )
)
